# bolek.net
KiCad netlist of a schematic drawn in EAGLE
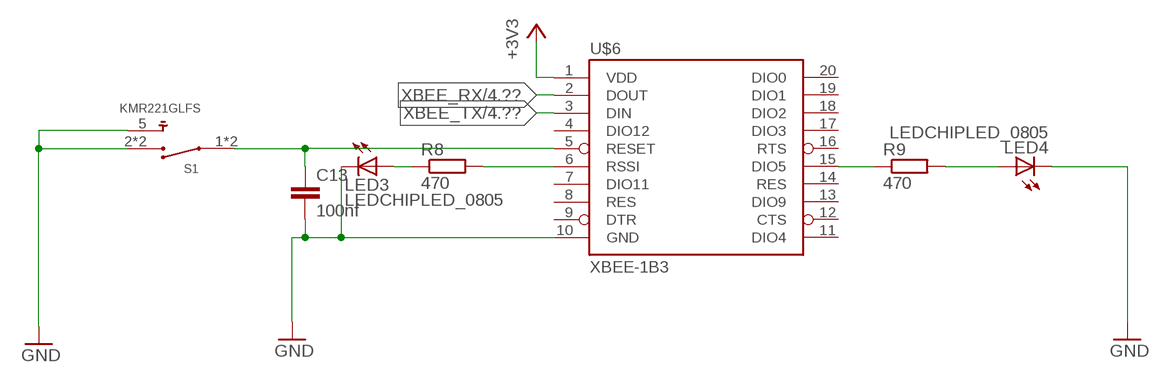
[diagram p0: schematic, sheet 1]
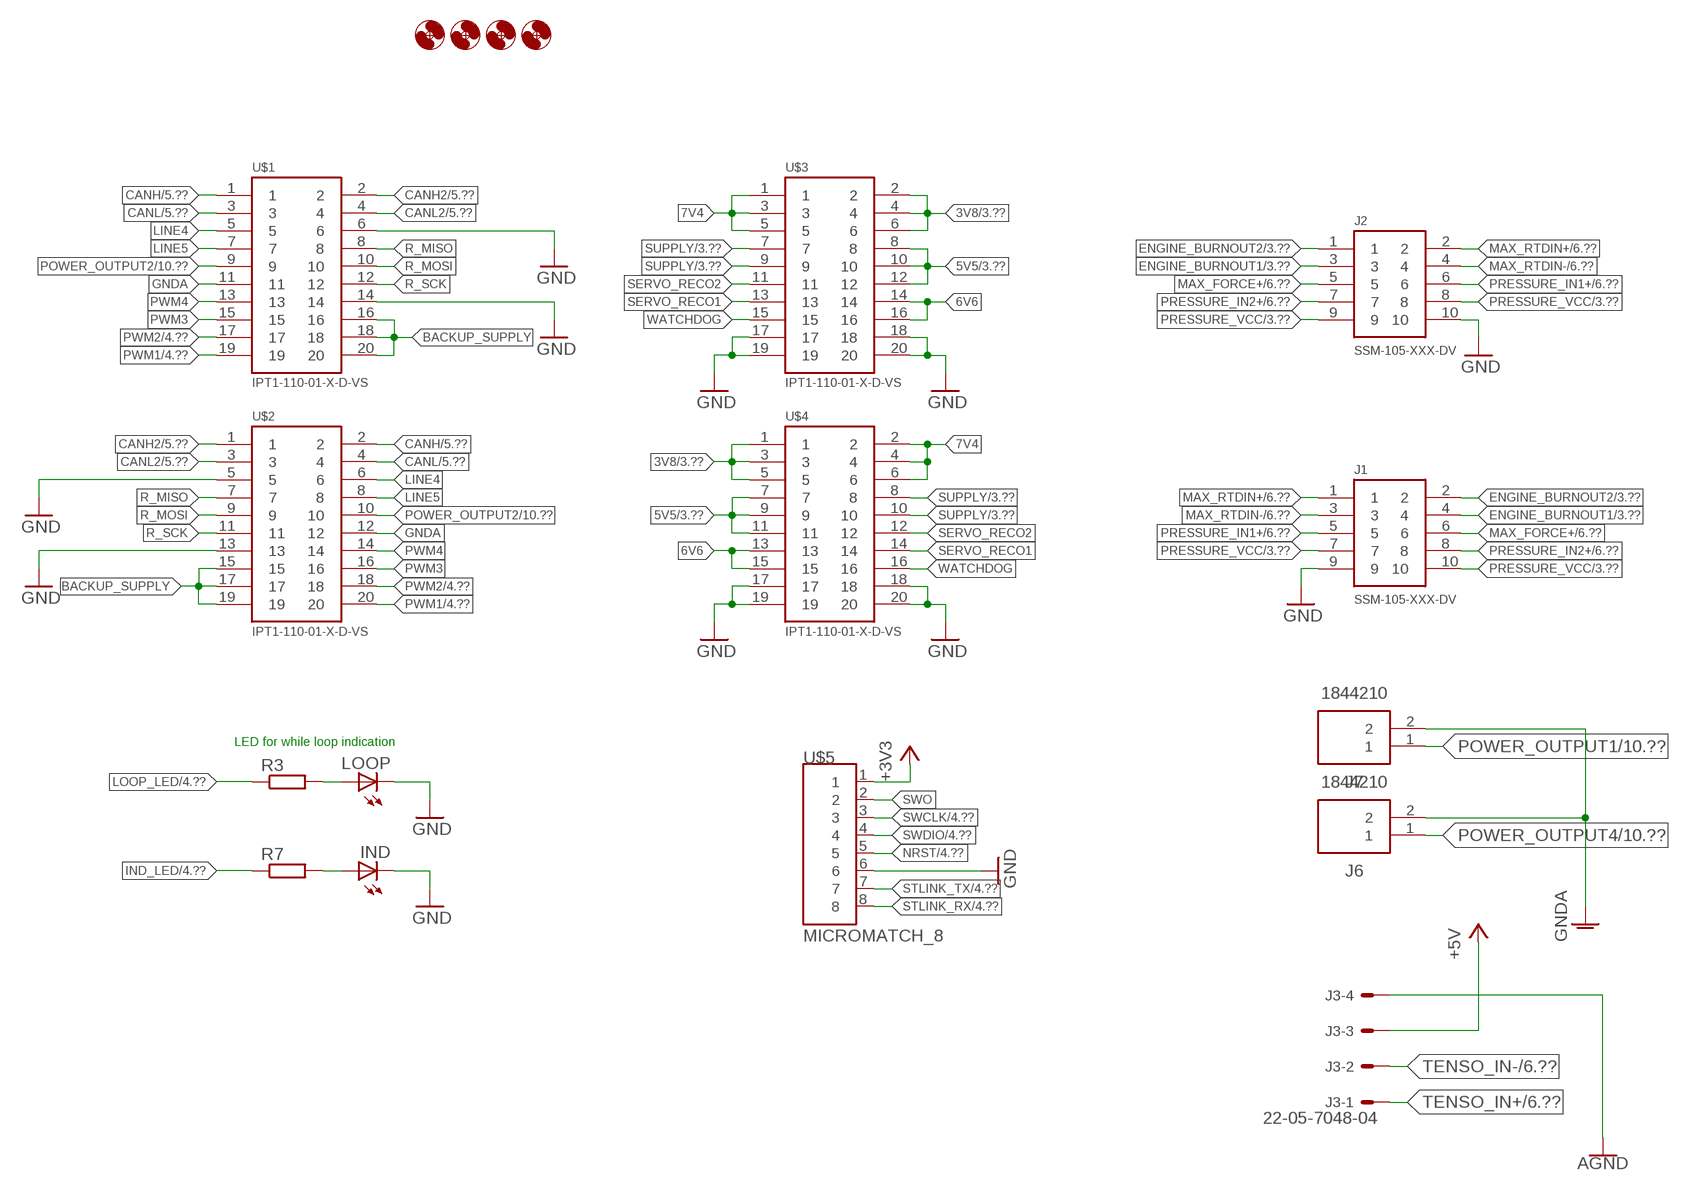
[diagram p1: schematic, sheet 2]
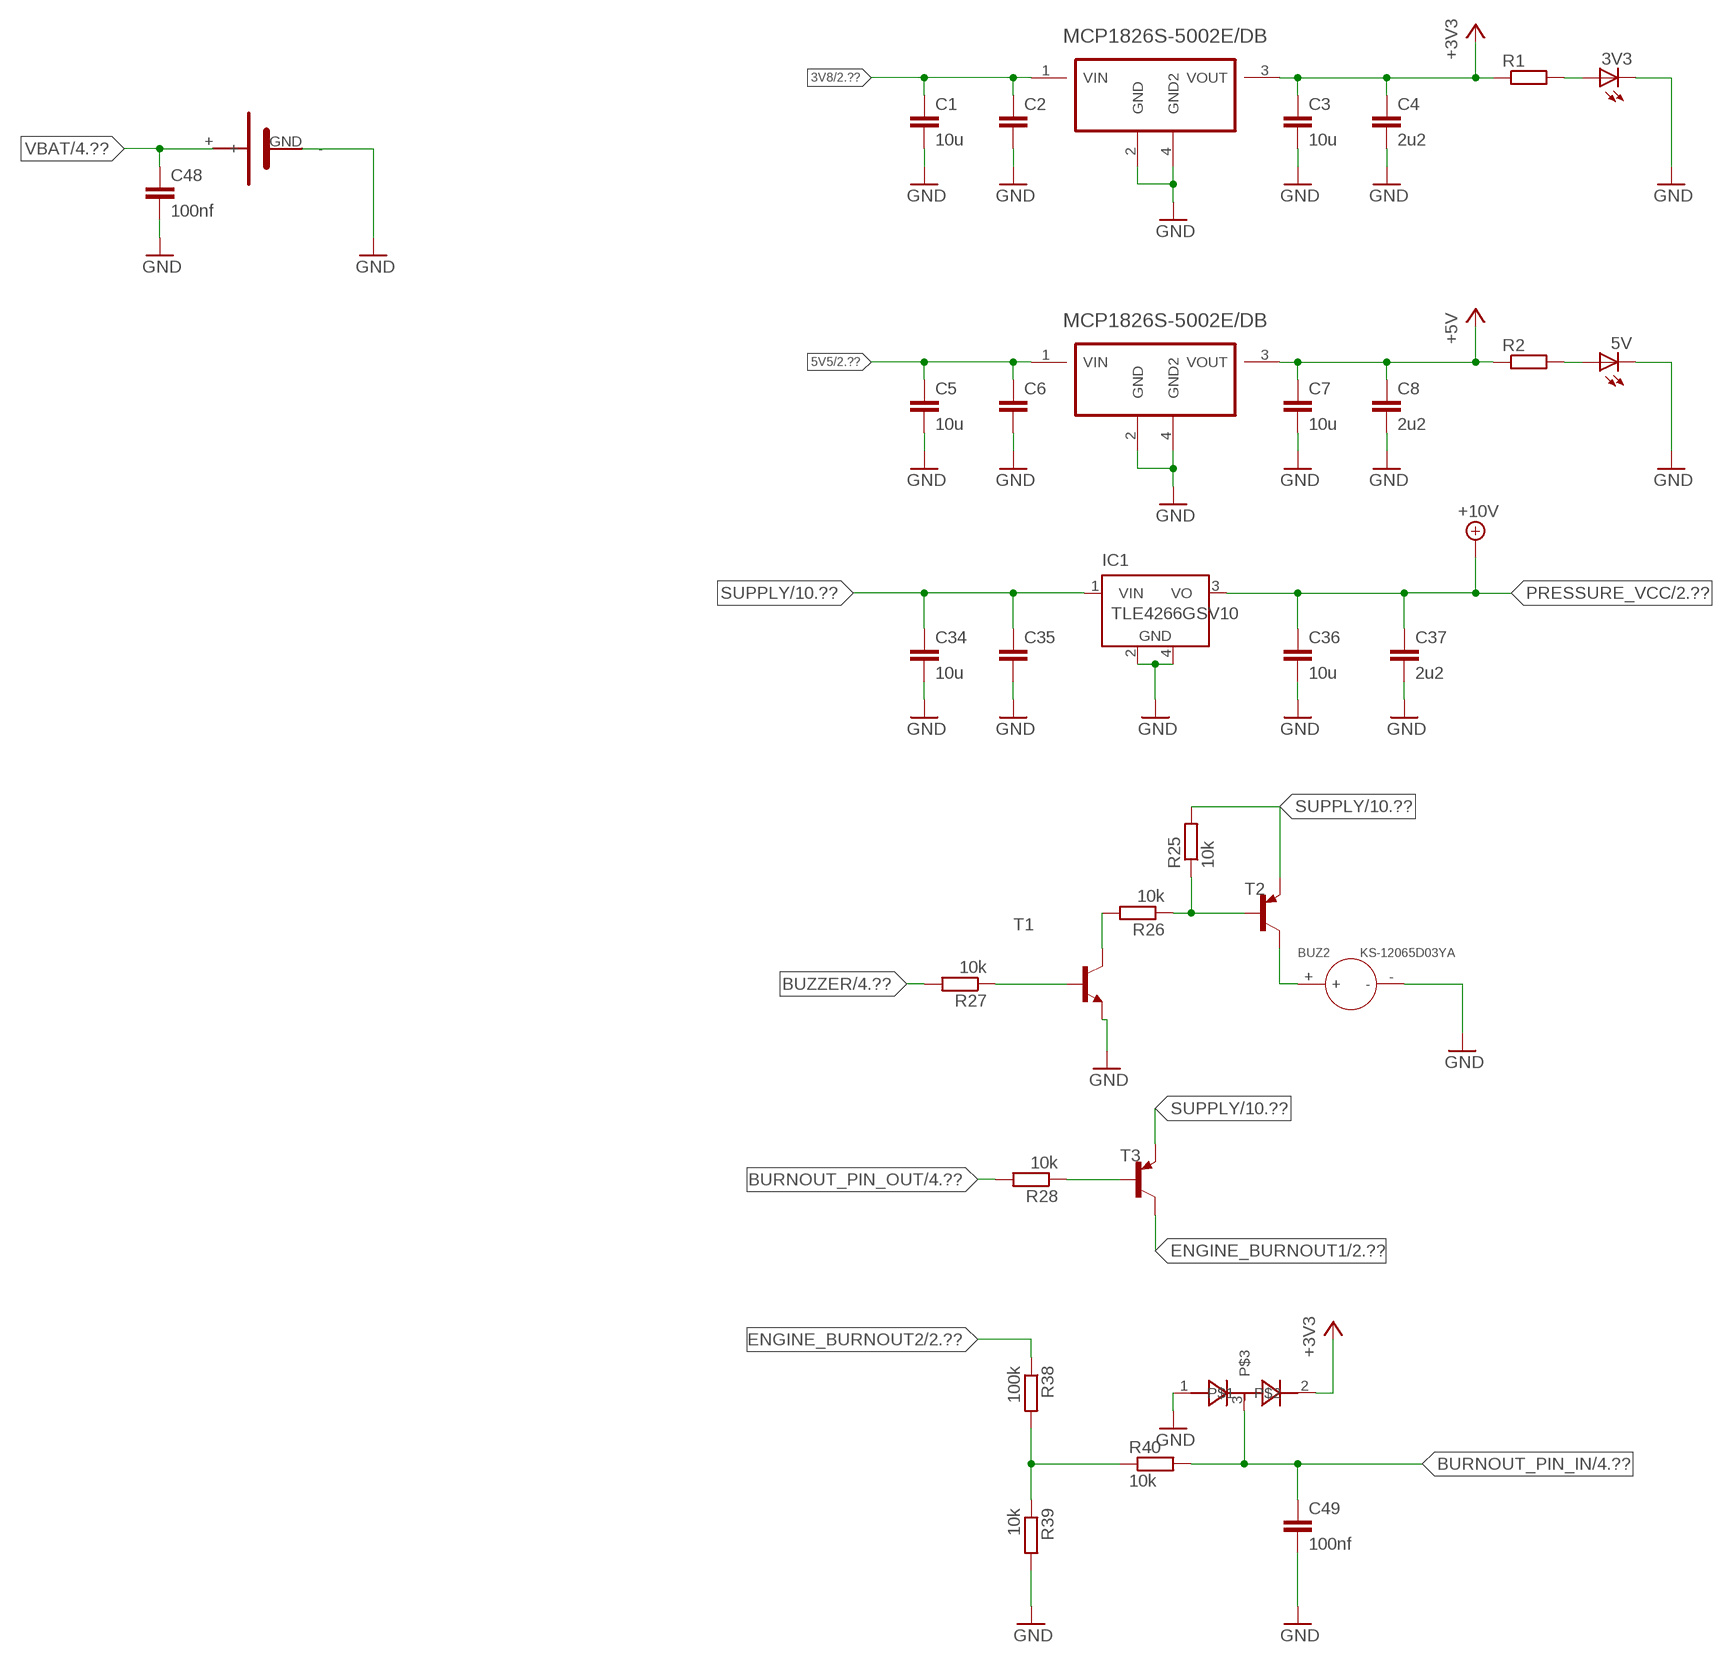
[diagram p2: schematic, sheet 3]
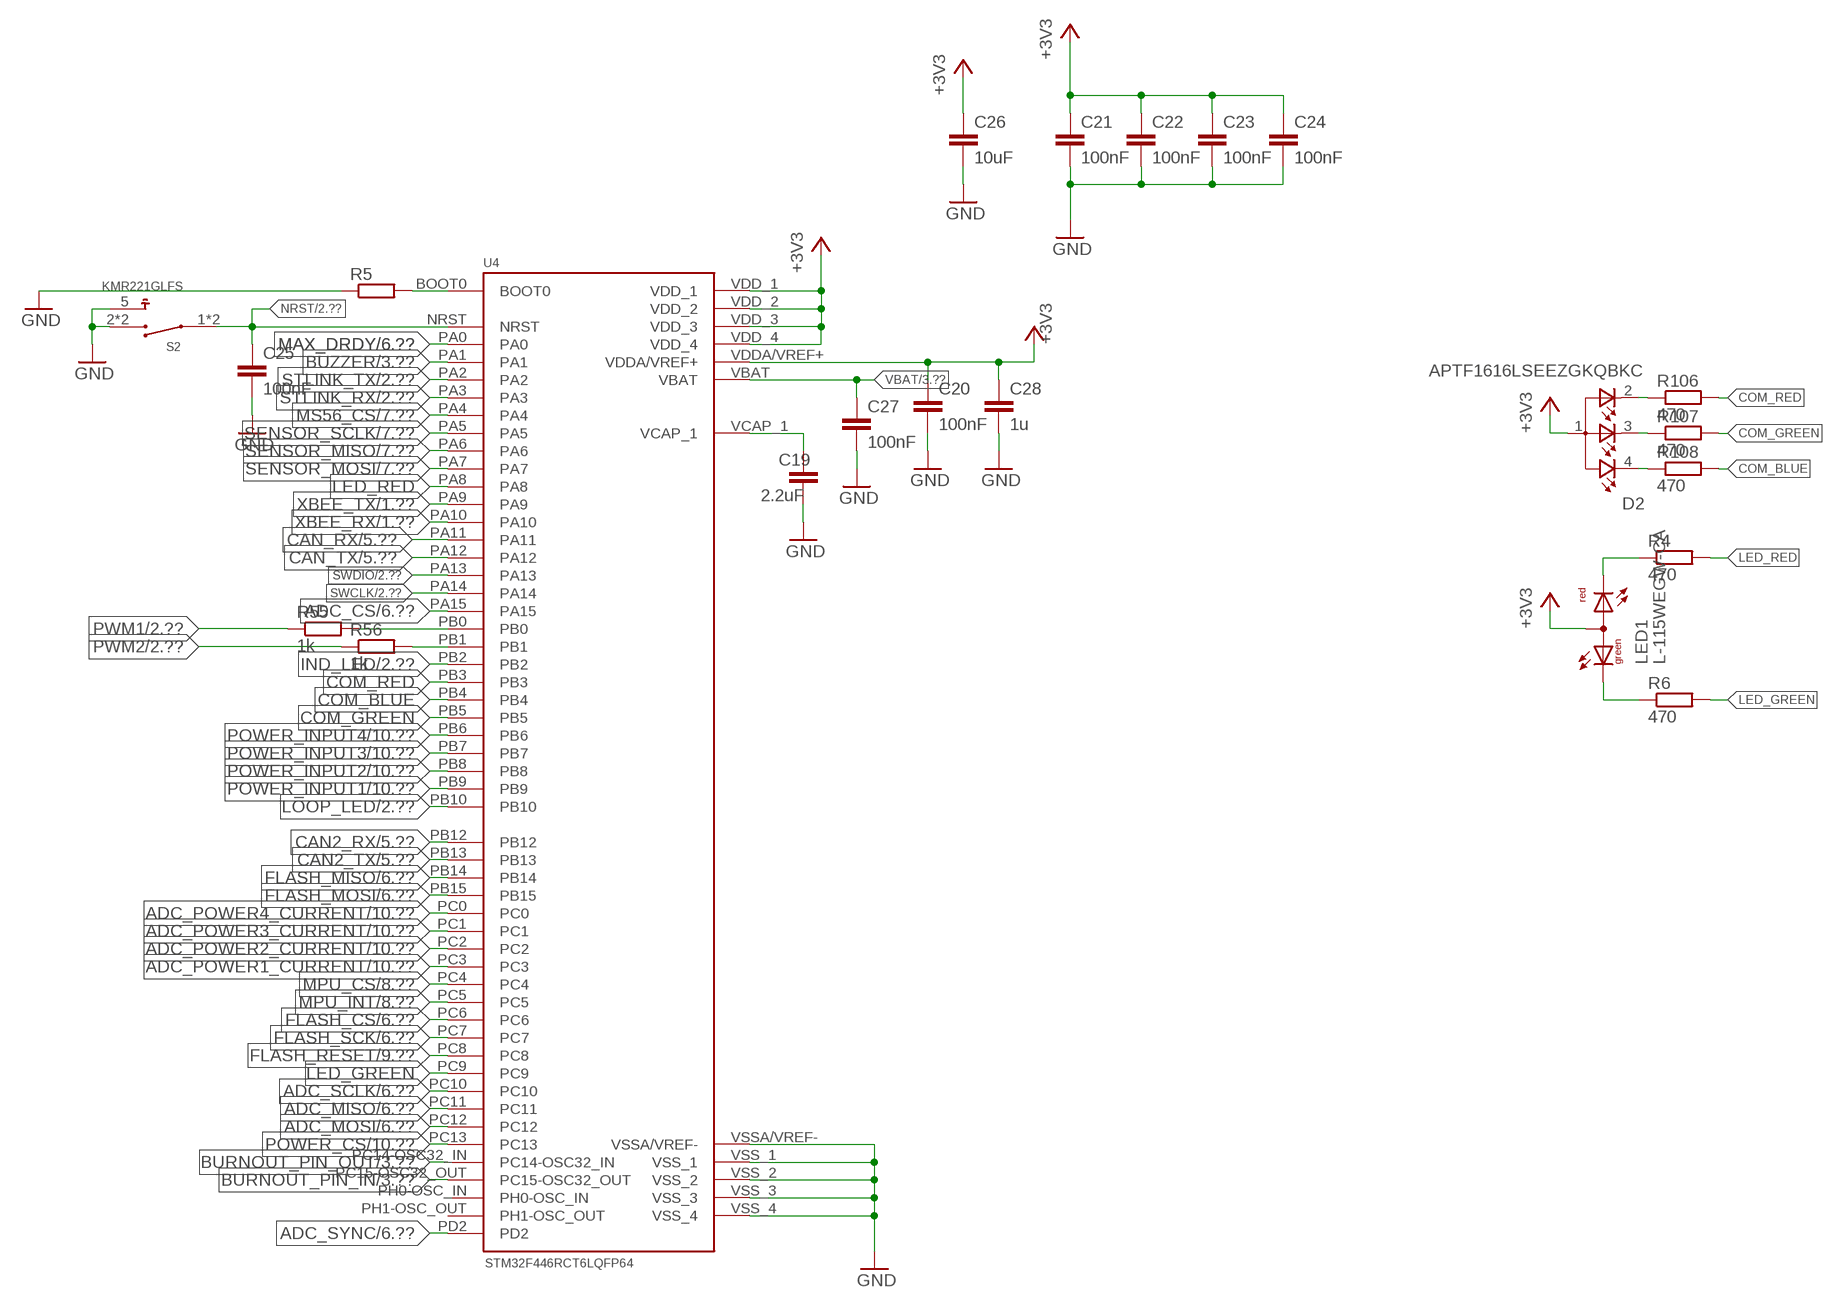
[diagram p3: schematic, sheet 4]
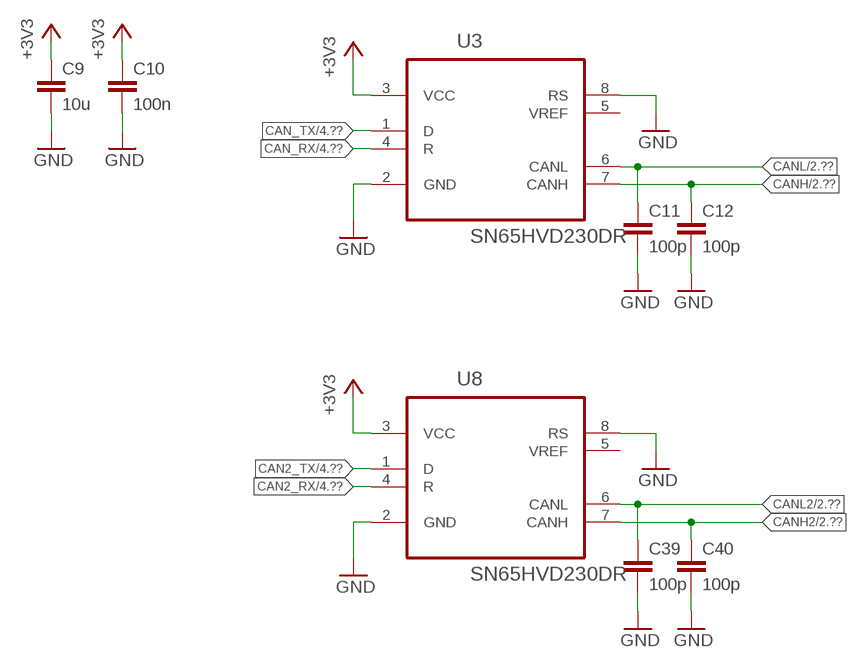
[diagram p4: schematic, sheet 5]
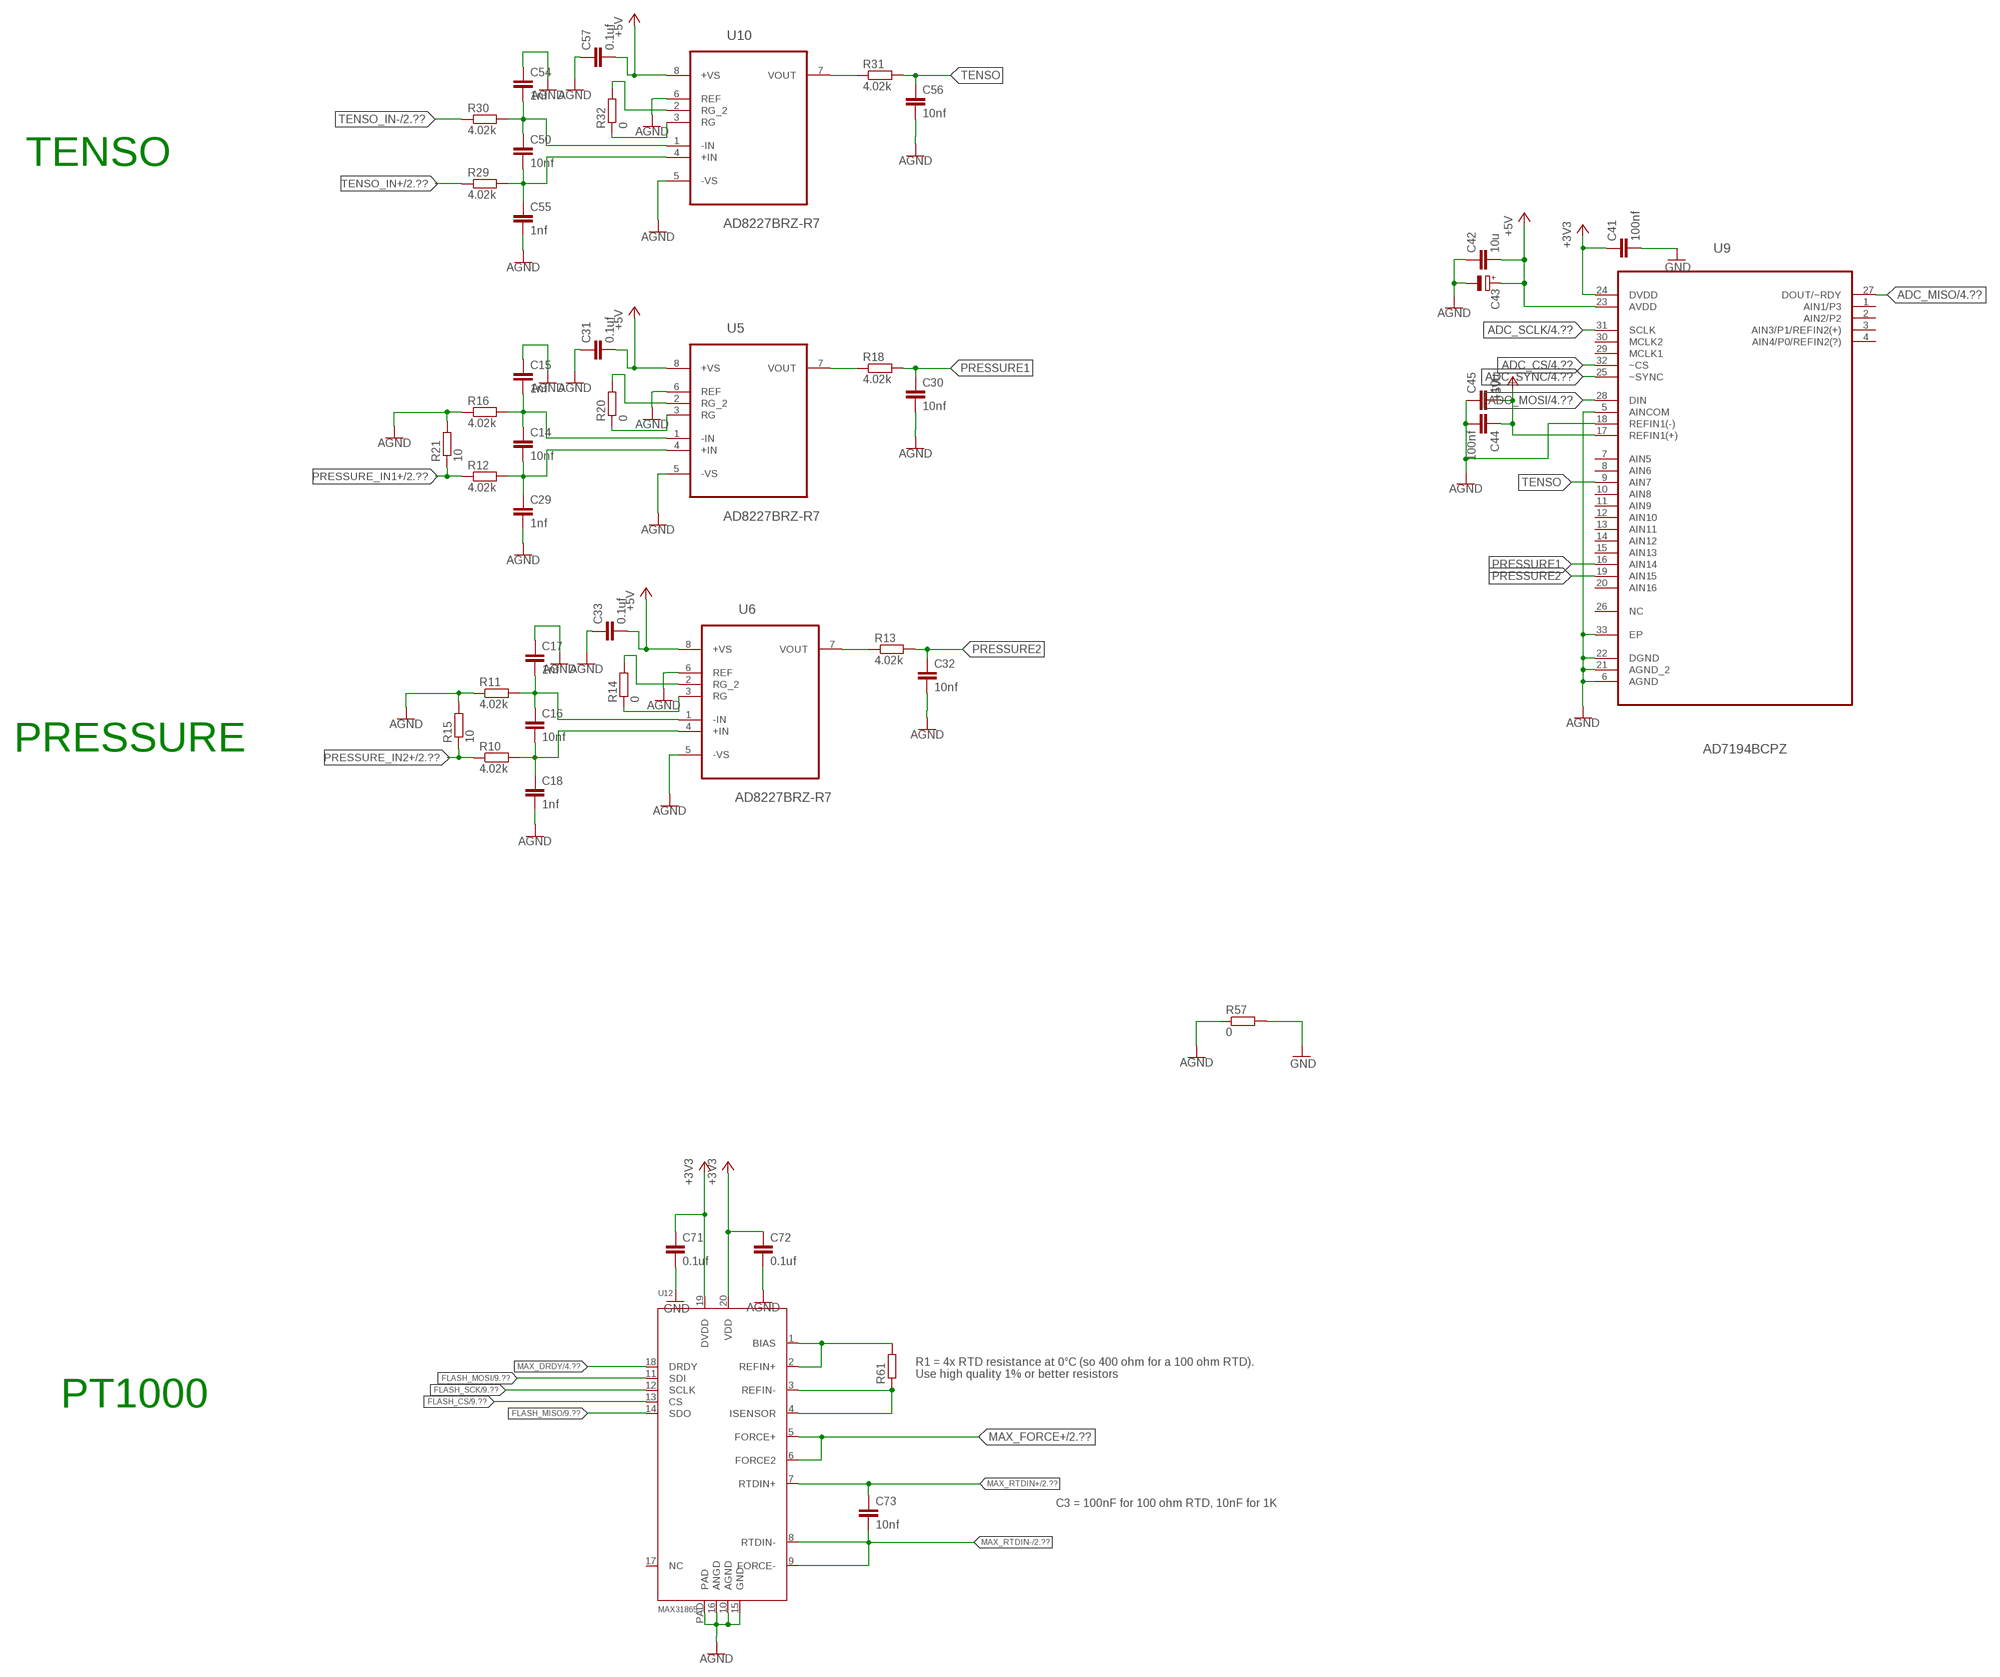
[diagram p5: schematic, sheet 6]
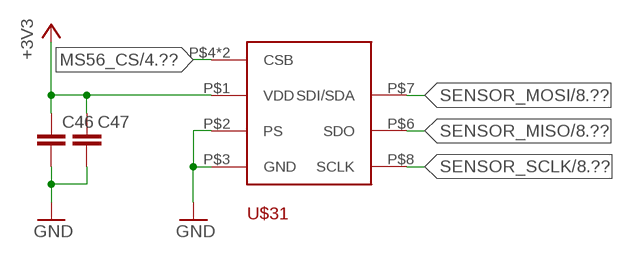
[diagram p6: schematic, sheet 7]
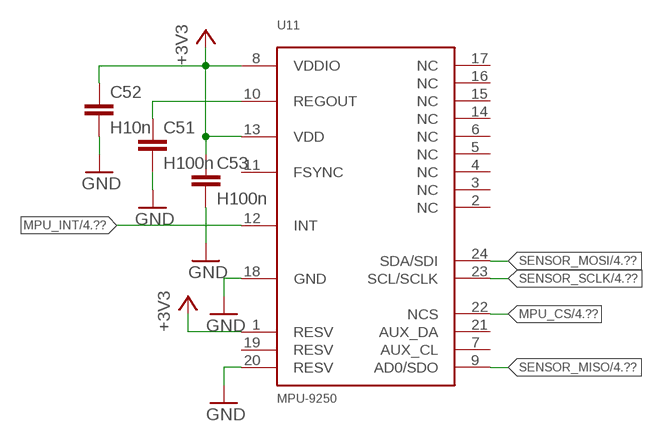
[diagram p7: schematic, sheet 8]
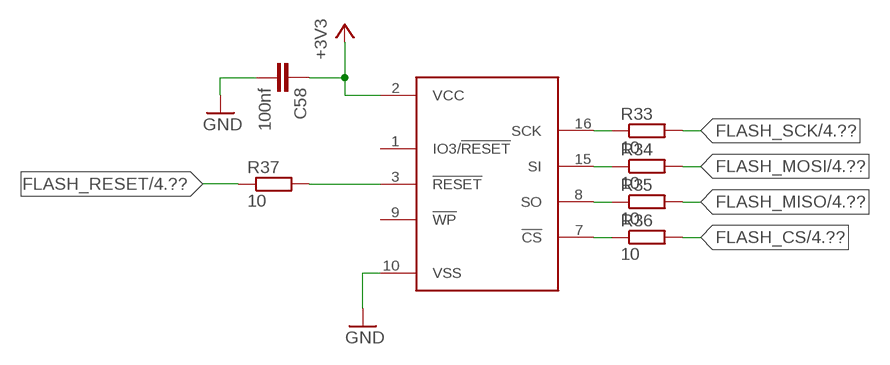
[diagram p8: schematic, sheet 9]
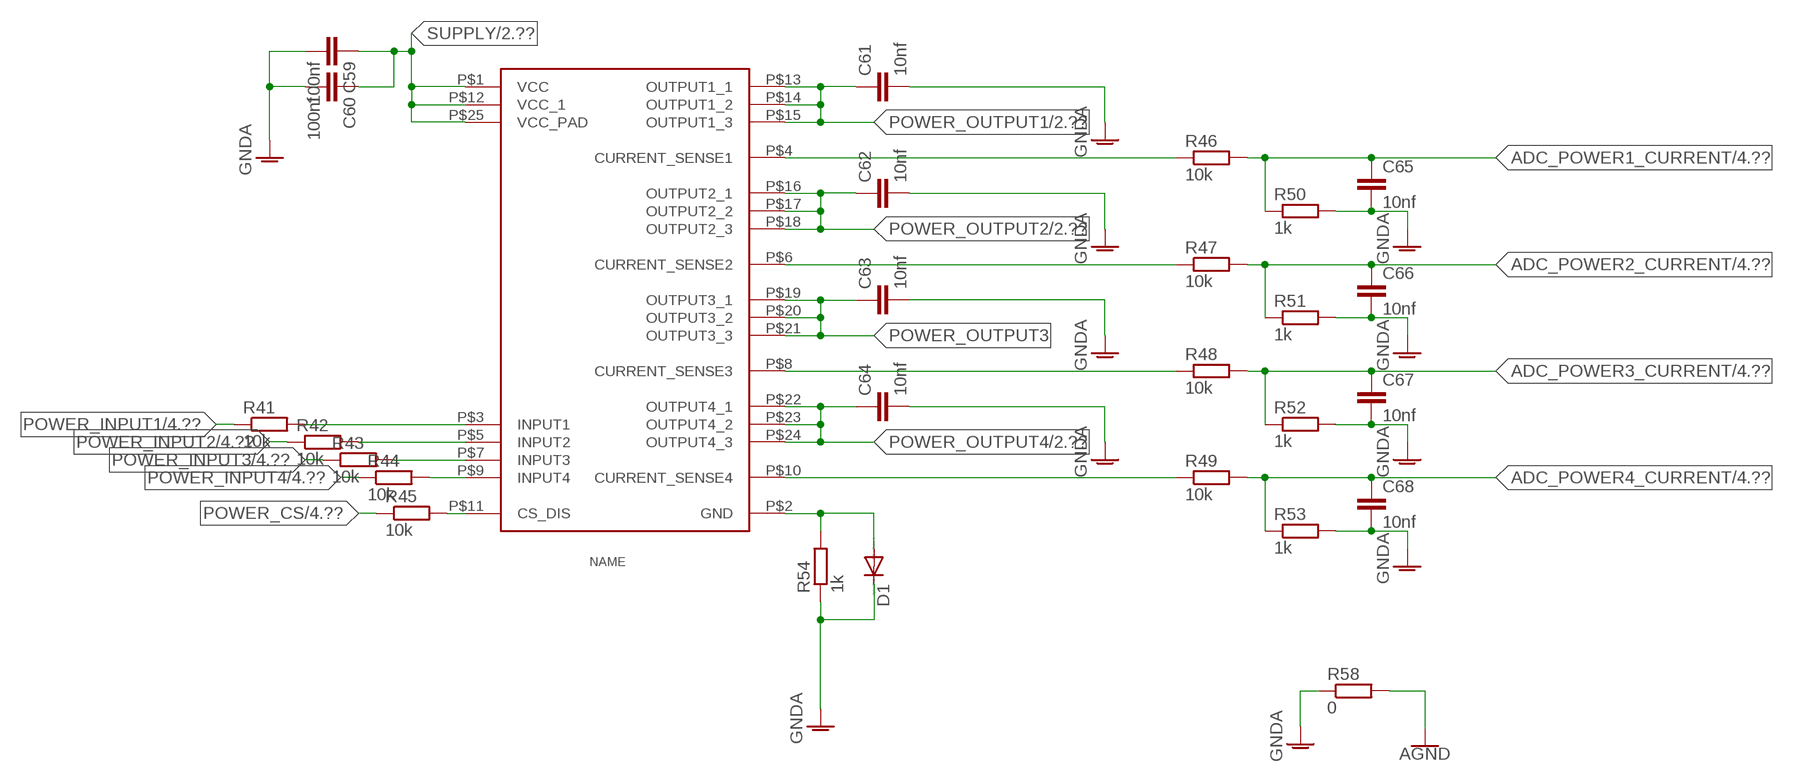
[diagram p9: schematic, sheet 10]

(export (version "E")
  (design (tool "Eeschema 10.0.6"))
  (components
    (comp (ref "C19")
      (value "2.2uF")
      (footprint "eagle-import:C0603K")
      (libsource (lib "eagle-import") (part "rcl_334_C-EUC0603K"))
    )
    (comp (ref "C20")
      (value "100nF")
      (footprint "eagle-import:C0603K")
      (libsource (lib "eagle-import") (part "rcl_334_C-EUC0603K"))
    )
    (comp (ref "C21")
      (value "100nF")
      (footprint "eagle-import:C0603K")
      (libsource (lib "eagle-import") (part "rcl_334_C-EUC0603K"))
    )
    (comp (ref "C22")
      (value "100nF")
      (footprint "eagle-import:C0603K")
      (libsource (lib "eagle-import") (part "rcl_334_C-EUC0603K"))
    )
    (comp (ref "C23")
      (value "100nF")
      (footprint "eagle-import:C0603K")
      (libsource (lib "eagle-import") (part "rcl_334_C-EUC0603K"))
    )
    (comp (ref "C24")
      (value "100nF")
      (footprint "eagle-import:C0603K")
      (libsource (lib "eagle-import") (part "rcl_334_C-EUC0603K"))
    )
    (comp (ref "C25")
      (value "100nF")
      (footprint "eagle-import:C0603K")
      (libsource (lib "eagle-import") (part "rcl_334_C-EUC0603K"))
    )
    (comp (ref "C26")
      (value "10uF")
      (footprint "eagle-import:C0805K")
      (libsource (lib "eagle-import") (part "rcl_334_C-EUC0805K"))
    )
    (comp (ref "C27")
      (value "100nF")
      (footprint "eagle-import:C0603K")
      (libsource (lib "eagle-import") (part "rcl_334_C-EUC0603K"))
    )
    (comp (ref "C28")
      (value "1u")
      (footprint "eagle-import:C0603K")
      (libsource (lib "eagle-import") (part "rcl_334_C-EUC0603K"))
    )
    (comp (ref "D2")
      (value "APTF1616LSEEZGKQBKC")
      (footprint "eagle-import:LEDSC160X160X070-4N")
      (fields (field (name "MF") "Kingbright"))
      (libsource (lib "eagle-import") (part "APTF1616LSEEZGKQBKC"))
    )
    (comp (ref "LED1")
      (value "L-115WEGW-CA")
      (footprint "eagle-import:DUOLED-A-3MM")
      (libsource (lib "eagle-import") (part "L-115WEGW-CA"))
    )
    (comp (ref "R4")
      (value "470")
      (footprint "eagle-import:R0603")
      (libsource (lib "eagle-import") (part "rcl_334_R-EU_R0603"))
    )
    (comp (ref "R5")
      (value "R-EU_R0603")
      (footprint "eagle-import:R0603")
      (libsource (lib "eagle-import") (part "rcl_334_R-EU_R0603"))
    )
    (comp (ref "R6")
      (value "470")
      (footprint "eagle-import:R0603")
      (libsource (lib "eagle-import") (part "rcl_334_R-EU_R0603"))
    )
    (comp (ref "R55")
      (value "1k")
      (footprint "eagle-import:R0603")
      (libsource (lib "eagle-import") (part "rcl_334_R-EU_R0603"))
    )
    (comp (ref "R56")
      (value "1k")
      (footprint "eagle-import:R0603")
      (libsource (lib "eagle-import") (part "rcl_334_R-EU_R0603"))
    )
    (comp (ref "R106")
      (value "470")
      (footprint "eagle-import:R0603")
      (libsource (lib "eagle-import") (part "rcl_334_R-EU_R0603"))
    )
    (comp (ref "R107")
      (value "470")
      (footprint "eagle-import:R0603")
      (libsource (lib "eagle-import") (part "rcl_334_R-EU_R0603"))
    )
    (comp (ref "R108")
      (value "470")
      (footprint "eagle-import:R0603")
      (libsource (lib "eagle-import") (part "rcl_334_R-EU_R0603"))
    )
    (comp (ref "S2")
      (value "KMR221GLFS")
      (footprint "eagle-import:SW_KMR221GLFS")
      (fields (field (name "MF") "C&K Components"))
      (libsource (lib "eagle-import") (part "KMR221GLFS"))
    )
    (comp (ref "U4")
      (value "STM32F446RCT6LQFP64")
      (footprint "eagle-import:QFP50P1290X1290X120-64")
      (libsource (lib "eagle-import") (part "STM32F446RCT6LQFP64"))
    )
    (comp (ref "C51")
      (value "H100n")
      (footprint "eagle-import:C0603K")
      (libsource (lib "eagle-import") (part "rcl_334_C-EUC0603K"))
    )
    (comp (ref "C52")
      (value "H10n")
      (footprint "eagle-import:C0603K")
      (libsource (lib "eagle-import") (part "rcl_334_C-EUC0603K"))
    )
    (comp (ref "C53")
      (value "H100n")
      (footprint "eagle-import:C0603K")
      (libsource (lib "eagle-import") (part "rcl_334_C-EUC0603K"))
    )
    (comp (ref "U11")
      (value "MPU-9250")
      (footprint "eagle-import:MPU-9250")
      (fields (field (name "MF") "InvenSense"))
      (libsource (lib "eagle-import") (part "MPU-9250"))
    )
    (comp (ref "C58")
      (value "100nf")
      (footprint "eagle-import:C0603")
      (libsource (lib "eagle-import") (part "rcl_334_C-EUC0603"))
    )
    (comp (ref "R33")
      (value "10")
      (footprint "eagle-import:R0603")
      (libsource (lib "eagle-import") (part "rcl_334_R-EU_R0603"))
    )
    (comp (ref "R34")
      (value "10")
      (footprint "eagle-import:R0603")
      (libsource (lib "eagle-import") (part "rcl_334_R-EU_R0603"))
    )
    (comp (ref "R35")
      (value "10")
      (footprint "eagle-import:R0603")
      (libsource (lib "eagle-import") (part "rcl_334_R-EU_R0603"))
    )
    (comp (ref "R36")
      (value "10")
      (footprint "eagle-import:R0603")
      (libsource (lib "eagle-import") (part "rcl_334_R-EU_R0603"))
    )
    (comp (ref "R37")
      (value "10")
      (footprint "eagle-import:R0603")
      (libsource (lib "eagle-import") (part "rcl_334_R-EU_R0603"))
    )
    (comp (ref "U$39")
      (value "S25FLX")
      (footprint "eagle-import:SOIC16")
      (libsource (lib "eagle-import") (part "S25FLX"))
    )
    (comp (ref "C14")
      (value "10nf")
      (footprint "eagle-import:C0603")
      (libsource (lib "eagle-import") (part "C-EUC0603"))
    )
    (comp (ref "C15")
      (value "1nf")
      (footprint "eagle-import:C0603")
      (libsource (lib "eagle-import") (part "C-EUC0603"))
    )
    (comp (ref "C16")
      (value "10nf")
      (footprint "eagle-import:C0603")
      (libsource (lib "eagle-import") (part "C-EUC0603"))
    )
    (comp (ref "C17")
      (value "1nf")
      (footprint "eagle-import:C0603")
      (libsource (lib "eagle-import") (part "C-EUC0603"))
    )
    (comp (ref "C18")
      (value "1nf")
      (footprint "eagle-import:C0603")
      (libsource (lib "eagle-import") (part "C-EUC0603"))
    )
    (comp (ref "C29")
      (value "1nf")
      (footprint "eagle-import:C0603")
      (libsource (lib "eagle-import") (part "C-EUC0603"))
    )
    (comp (ref "C30")
      (value "10nf")
      (footprint "eagle-import:C0603")
      (libsource (lib "eagle-import") (part "C-EUC0603"))
    )
    (comp (ref "C31")
      (value "0.1uf")
      (footprint "eagle-import:C0603")
      (libsource (lib "eagle-import") (part "C-EUC0603"))
    )
    (comp (ref "C32")
      (value "10nf")
      (footprint "eagle-import:C0603")
      (libsource (lib "eagle-import") (part "C-EUC0603"))
    )
    (comp (ref "C33")
      (value "0.1uf")
      (footprint "eagle-import:C0603")
      (libsource (lib "eagle-import") (part "C-EUC0603"))
    )
    (comp (ref "C41")
      (value "100nf")
      (footprint "eagle-import:C0603K")
      (libsource (lib "eagle-import") (part "rcl_334_C-EUC0603K"))
    )
    (comp (ref "C42")
      (value "10u")
      (footprint "eagle-import:C0805K")
      (libsource (lib "eagle-import") (part "rcl_334_C-EUC0805K"))
    )
    (comp (ref "C43")
      (value "CPOL-EUSMCA")
      (footprint "eagle-import:SMC_A")
      (libsource (lib "eagle-import") (part "CPOL-EUSMCA"))
    )
    (comp (ref "C44")
      (value "100nf")
      (footprint "eagle-import:C0603K")
      (libsource (lib "eagle-import") (part "rcl_334_C-EUC0603K"))
    )
    (comp (ref "C45")
      (value "10u")
      (footprint "eagle-import:C0805K")
      (libsource (lib "eagle-import") (part "rcl_334_C-EUC0805K"))
    )
    (comp (ref "C50")
      (value "10nf")
      (footprint "eagle-import:C0603")
      (libsource (lib "eagle-import") (part "C-EUC0603"))
    )
    (comp (ref "C54")
      (value "1nf")
      (footprint "eagle-import:C0603")
      (libsource (lib "eagle-import") (part "C-EUC0603"))
    )
    (comp (ref "C55")
      (value "1nf")
      (footprint "eagle-import:C0603")
      (libsource (lib "eagle-import") (part "C-EUC0603"))
    )
    (comp (ref "C56")
      (value "10nf")
      (footprint "eagle-import:C0603")
      (libsource (lib "eagle-import") (part "C-EUC0603"))
    )
    (comp (ref "C57")
      (value "0.1uf")
      (footprint "eagle-import:C0603")
      (libsource (lib "eagle-import") (part "C-EUC0603"))
    )
    (comp (ref "C71")
      (value "0.1uf")
      (footprint "eagle-import:C0603")
      (libsource (lib "eagle-import") (part "rcl_334_C-EUC0603"))
    )
    (comp (ref "C72")
      (value "0.1uf")
      (footprint "eagle-import:C0603")
      (libsource (lib "eagle-import") (part "rcl_334_C-EUC0603"))
    )
    (comp (ref "C73")
      (value "10nf")
      (footprint "eagle-import:C0603")
      (libsource (lib "eagle-import") (part "rcl_334_C-EUC0603"))
    )
    (comp (ref "R10")
      (value "4.02k")
      (footprint "eagle-import:R0603")
      (libsource (lib "eagle-import") (part "R-EU_R0603"))
    )
    (comp (ref "R11")
      (value "4.02k")
      (footprint "eagle-import:R0603")
      (libsource (lib "eagle-import") (part "R-EU_R0603"))
    )
    (comp (ref "R12")
      (value "4.02k")
      (footprint "eagle-import:R0603")
      (libsource (lib "eagle-import") (part "R-EU_R0603"))
    )
    (comp (ref "R13")
      (value "4.02k")
      (footprint "eagle-import:R0603")
      (libsource (lib "eagle-import") (part "R-EU_R0603"))
    )
    (comp (ref "R14")
      (value "0")
      (footprint "eagle-import:R0805")
      (libsource (lib "eagle-import") (part "R-EU_R0805"))
    )
    (comp (ref "R15")
      (value "10")
      (footprint "eagle-import:R0603")
      (libsource (lib "eagle-import") (part "R-EU_R0603"))
    )
    (comp (ref "R16")
      (value "4.02k")
      (footprint "eagle-import:R0603")
      (libsource (lib "eagle-import") (part "R-EU_R0603"))
    )
    (comp (ref "R18")
      (value "4.02k")
      (footprint "eagle-import:R0603")
      (libsource (lib "eagle-import") (part "R-EU_R0603"))
    )
    (comp (ref "R20")
      (value "0")
      (footprint "eagle-import:R0805")
      (libsource (lib "eagle-import") (part "R-EU_R0805"))
    )
    (comp (ref "R21")
      (value "10")
      (footprint "eagle-import:R0603")
      (libsource (lib "eagle-import") (part "R-EU_R0603"))
    )
    (comp (ref "R29")
      (value "4.02k")
      (footprint "eagle-import:R0603")
      (libsource (lib "eagle-import") (part "R-EU_R0603"))
    )
    (comp (ref "R30")
      (value "4.02k")
      (footprint "eagle-import:R0603")
      (libsource (lib "eagle-import") (part "R-EU_R0603"))
    )
    (comp (ref "R31")
      (value "4.02k")
      (footprint "eagle-import:R0603")
      (libsource (lib "eagle-import") (part "R-EU_R0603"))
    )
    (comp (ref "R32")
      (value "0")
      (footprint "eagle-import:R0805")
      (libsource (lib "eagle-import") (part "R-EU_R0805"))
    )
    (comp (ref "R57")
      (value "0")
      (footprint "eagle-import:R0603")
      (libsource (lib "eagle-import") (part "rcl_334_R-EU_R0603"))
    )
    (comp (ref "R61")
      (value "R-EU_R0805")
      (footprint "eagle-import:R0805")
      (libsource (lib "eagle-import") (part "rcl_334_R-EU_R0805"))
    )
    (comp (ref "U5")
      (value "AD8227BRZ-R7")
      (footprint "eagle-import:SOIC127P600X175-8N")
      (libsource (lib "eagle-import") (part "AD8227BRZ-R7"))
    )
    (comp (ref "U6")
      (value "AD8227BRZ-R7")
      (footprint "eagle-import:SOIC127P600X175-8N")
      (libsource (lib "eagle-import") (part "AD8227BRZ-R7"))
    )
    (comp (ref "U9")
      (value "AD7194BCPZ")
      (footprint "eagle-import:QFN50P500X500X80-33N")
      (libsource (lib "eagle-import") (part "AD7194BCPZ"))
    )
    (comp (ref "U10")
      (value "AD8227BRZ-R7")
      (footprint "eagle-import:SOIC127P600X175-8N")
      (libsource (lib "eagle-import") (part "AD8227BRZ-R7"))
    )
    (comp (ref "U12")
      (value "MAX31865")
      (footprint "eagle-import:QFN20_4MM_0.65MM")
      (libsource (lib "eagle-import") (part "TEMP_MAX31865"))
    )
    (comp (ref "H1")
      (value "MOUNT-HOLE3.2")
      (footprint "eagle-import:3,2")
      (libsource (lib "eagle-import") (part "MOUNT-HOLE3.2"))
    )
    (comp (ref "H2")
      (value "MOUNT-HOLE3.2")
      (footprint "eagle-import:3,2")
      (libsource (lib "eagle-import") (part "MOUNT-HOLE3.2"))
    )
    (comp (ref "H3")
      (value "MOUNT-HOLE3.2")
      (footprint "eagle-import:3,2")
      (libsource (lib "eagle-import") (part "MOUNT-HOLE3.2"))
    )
    (comp (ref "H4")
      (value "MOUNT-HOLE3.2")
      (footprint "eagle-import:3,2")
      (libsource (lib "eagle-import") (part "MOUNT-HOLE3.2"))
    )
    (comp (ref "IND")
      (value "LEDCHIPLED_0603")
      (footprint "eagle-import:CHIPLED_0603")
      (libsource (lib "eagle-import") (part "LEDCHIPLED_0603"))
    )
    (comp (ref "J1")
      (value "SSM-105-XXX-DV")
      (footprint "eagle-import:SSM-105-XXX-DV")
      (fields (field (name "MF") "Samtec"))
      (libsource (lib "eagle-import") (part "SSM-105-XXX-DV"))
    )
    (comp (ref "J2")
      (value "SSM-105-XXX-DV")
      (footprint "eagle-import:SSM-105-XXX-DV")
      (fields (field (name "MF") "Samtec"))
      (libsource (lib "eagle-import") (part "SSM-105-XXX-DV"))
    )
    (comp (ref "J3")
      (value "22-05-7048-04")
      (footprint "eagle-import:7395-04")
      (fields (field (name "MF") "MOLEX"))
      (libsource (lib "eagle-import") (part "22-?-0405-7048"))
    )
    (comp (ref "J6")
      (value "1844210")
      (footprint "eagle-import:SHDR2W100P0X350_1X2_840X920X72")
      (fields (field (name "RS_PART_NUMBER") "8042248"))
      (libsource (lib "eagle-import") (part "1844210"))
    )
    (comp (ref "J7")
      (value "1844210")
      (footprint "eagle-import:SHDR2W100P0X350_1X2_840X920X72")
      (fields (field (name "RS_PART_NUMBER") "8042248"))
      (libsource (lib "eagle-import") (part "1844210"))
    )
    (comp (ref "LOOP")
      (value "LEDCHIPLED_0603")
      (footprint "eagle-import:CHIPLED_0603")
      (libsource (lib "eagle-import") (part "LEDCHIPLED_0603"))
    )
    (comp (ref "R3")
      (value "R-EU_R0603")
      (footprint "eagle-import:R0603")
      (libsource (lib "eagle-import") (part "rcl_334_R-EU_R0603"))
    )
    (comp (ref "R7")
      (value "R-EU_R0603")
      (footprint "eagle-import:R0603")
      (libsource (lib "eagle-import") (part "rcl_334_R-EU_R0603"))
    )
    (comp (ref "U$1")
      (value "IPT1-110-01-X-D-VS")
      (footprint "eagle-import:IPT1-110-01-X-D-VS")
      (fields (field (name "MF") "Samtec") (field (name "MP") "IPT1-110--01-S-D-VS-"))
      (libsource (lib "eagle-import") (part "IPT1-110-01-X-D-VS"))
    )
    (comp (ref "U$2")
      (value "IPT1-110-01-X-D-VS")
      (footprint "eagle-import:IPT1-110-01-X-D-VS")
      (fields (field (name "MF") "Samtec") (field (name "MP") "IPT1-110--01-S-D-VS-"))
      (libsource (lib "eagle-import") (part "IPT1-110-01-X-D-VS"))
    )
    (comp (ref "U$3")
      (value "IPT1-110-01-X-D-VS")
      (footprint "eagle-import:IPT1-110-01-X-D-VS")
      (fields (field (name "MF") "Samtec") (field (name "MP") "IPT1-110--01-S-D-VS-"))
      (libsource (lib "eagle-import") (part "IPT1-110-01-X-D-VS"))
    )
    (comp (ref "U$4")
      (value "IPT1-110-01-X-D-VS")
      (footprint "eagle-import:IPT1-110-01-X-D-VS")
      (fields (field (name "MF") "Samtec") (field (name "MP") "IPT1-110--01-S-D-VS-"))
      (libsource (lib "eagle-import") (part "IPT1-110-01-X-D-VS"))
    )
    (comp (ref "U$5")
      (value "MICROMATCH_8")
      (footprint "eagle-import:MICROMATCH_8")
      (libsource (lib "eagle-import") (part "MICROMATCH_8"))
    )
    (comp (ref "C59")
      (value "100nf")
      (footprint "eagle-import:C0603")
      (libsource (lib "eagle-import") (part "rcl_334_C-EUC0603"))
    )
    (comp (ref "C60")
      (value "100nf")
      (footprint "eagle-import:C0603")
      (libsource (lib "eagle-import") (part "rcl_334_C-EUC0603"))
    )
    (comp (ref "C61")
      (value "10nf")
      (footprint "eagle-import:C0603")
      (libsource (lib "eagle-import") (part "rcl_334_C-EUC0603"))
    )
    (comp (ref "C62")
      (value "10nf")
      (footprint "eagle-import:C0603")
      (libsource (lib "eagle-import") (part "rcl_334_C-EUC0603"))
    )
    (comp (ref "C63")
      (value "10nf")
      (footprint "eagle-import:C0603")
      (libsource (lib "eagle-import") (part "rcl_334_C-EUC0603"))
    )
    (comp (ref "C64")
      (value "10nf")
      (footprint "eagle-import:C0603")
      (libsource (lib "eagle-import") (part "rcl_334_C-EUC0603"))
    )
    (comp (ref "C65")
      (value "10nf")
      (footprint "eagle-import:C0603")
      (libsource (lib "eagle-import") (part "rcl_334_C-EUC0603"))
    )
    (comp (ref "C66")
      (value "10nf")
      (footprint "eagle-import:C0603")
      (libsource (lib "eagle-import") (part "rcl_334_C-EUC0603"))
    )
    (comp (ref "C67")
      (value "10nf")
      (footprint "eagle-import:C0603")
      (libsource (lib "eagle-import") (part "rcl_334_C-EUC0603"))
    )
    (comp (ref "C68")
      (value "10nf")
      (footprint "eagle-import:C0603")
      (libsource (lib "eagle-import") (part "rcl_334_C-EUC0603"))
    )
    (comp (ref "D1")
      (value "DIODE-SOD123")
      (footprint "eagle-import:SOD123")
      (libsource (lib "eagle-import") (part "DIODE-SOD123"))
    )
    (comp (ref "R41")
      (value "10k")
      (footprint "eagle-import:R0603")
      (libsource (lib "eagle-import") (part "rcl_334_R-EU_R0603"))
    )
    (comp (ref "R42")
      (value "10k")
      (footprint "eagle-import:R0603")
      (libsource (lib "eagle-import") (part "rcl_334_R-EU_R0603"))
    )
    (comp (ref "R43")
      (value "10k")
      (footprint "eagle-import:R0603")
      (libsource (lib "eagle-import") (part "rcl_334_R-EU_R0603"))
    )
    (comp (ref "R44")
      (value "10k")
      (footprint "eagle-import:R0603")
      (libsource (lib "eagle-import") (part "rcl_334_R-EU_R0603"))
    )
    (comp (ref "R45")
      (value "10k")
      (footprint "eagle-import:R0603")
      (libsource (lib "eagle-import") (part "rcl_334_R-EU_R0603"))
    )
    (comp (ref "R46")
      (value "10k")
      (footprint "eagle-import:R0603")
      (libsource (lib "eagle-import") (part "rcl_334_R-EU_R0603"))
    )
    (comp (ref "R47")
      (value "10k")
      (footprint "eagle-import:R0603")
      (libsource (lib "eagle-import") (part "rcl_334_R-EU_R0603"))
    )
    (comp (ref "R48")
      (value "10k")
      (footprint "eagle-import:R0603")
      (libsource (lib "eagle-import") (part "rcl_334_R-EU_R0603"))
    )
    (comp (ref "R49")
      (value "10k")
      (footprint "eagle-import:R0603")
      (libsource (lib "eagle-import") (part "rcl_334_R-EU_R0603"))
    )
    (comp (ref "R50")
      (value "1k")
      (footprint "eagle-import:R0603")
      (libsource (lib "eagle-import") (part "rcl_334_R-EU_R0603"))
    )
    (comp (ref "R51")
      (value "1k")
      (footprint "eagle-import:R0603")
      (libsource (lib "eagle-import") (part "rcl_334_R-EU_R0603"))
    )
    (comp (ref "R52")
      (value "1k")
      (footprint "eagle-import:R0603")
      (libsource (lib "eagle-import") (part "rcl_334_R-EU_R0603"))
    )
    (comp (ref "R53")
      (value "1k")
      (footprint "eagle-import:R0603")
      (libsource (lib "eagle-import") (part "rcl_334_R-EU_R0603"))
    )
    (comp (ref "R54")
      (value "1k")
      (footprint "eagle-import:R0603")
      (libsource (lib "eagle-import") (part "rcl_334_R-EU_R0603"))
    )
    (comp (ref "R58")
      (value "0")
      (footprint "eagle-import:R0603")
      (libsource (lib "eagle-import") (part "rcl_334_R-EU_R0603"))
    )
    (comp (ref "VNQ5027AK-E1")
      (value "VNQ5027AK-E")
      (footprint "eagle-import:POWERSSO-24")
      (libsource (lib "eagle-import") (part "VNQ5027AK-E"))
    )
    (comp (ref "C46")
      (value "C-EUC0603")
      (footprint "eagle-import:C0603")
      (libsource (lib "eagle-import") (part "rcl_334_C-EUC0603"))
    )
    (comp (ref "C47")
      (value "C-EUC0603")
      (footprint "eagle-import:C0603")
      (libsource (lib "eagle-import") (part "rcl_334_C-EUC0603"))
    )
    (comp (ref "U$31")
      (value "MS56XX")
      (footprint "eagle-import:MS56XX")
      (libsource (lib "eagle-import") (part "MS56XX"))
    )
    (comp (ref "C9")
      (value "10u")
      (footprint "eagle-import:C0805K")
      (libsource (lib "eagle-import") (part "rcl_334_C-EUC0805K"))
    )
    (comp (ref "C10")
      (value "100n")
      (footprint "eagle-import:C0603K")
      (libsource (lib "eagle-import") (part "rcl_334_C-EUC0603K"))
    )
    (comp (ref "C11")
      (value "100p")
      (footprint "eagle-import:C0603K")
      (libsource (lib "eagle-import") (part "rcl_334_C-EUC0603K"))
    )
    (comp (ref "C12")
      (value "100p")
      (footprint "eagle-import:C0603K")
      (libsource (lib "eagle-import") (part "rcl_334_C-EUC0603K"))
    )
    (comp (ref "C39")
      (value "100p")
      (footprint "eagle-import:C0603K")
      (libsource (lib "eagle-import") (part "rcl_334_C-EUC0603K"))
    )
    (comp (ref "C40")
      (value "100p")
      (footprint "eagle-import:C0603K")
      (libsource (lib "eagle-import") (part "rcl_334_C-EUC0603K"))
    )
    (comp (ref "U3")
      (value "SN65HVD230DR")
      (footprint "eagle-import:SOIC127P600X175-8N")
      (fields (field (name "MF") "Texas Instruments"))
      (libsource (lib "eagle-import") (part "SN65HVD230DR"))
    )
    (comp (ref "U8")
      (value "SN65HVD230DR")
      (footprint "eagle-import:SOIC127P600X175-8N")
      (fields (field (name "MF") "Texas Instruments"))
      (libsource (lib "eagle-import") (part "SN65HVD230DR"))
    )
    (comp (ref "C13")
      (value "100nf")
      (footprint "eagle-import:C0603")
      (libsource (lib "eagle-import") (part "rcl_334_C-EUC0603"))
    )
    (comp (ref "LED3")
      (value "LEDCHIPLED_0805")
      (footprint "eagle-import:CHIPLED_0805")
      (libsource (lib "eagle-import") (part "audio amplifier example_970892_LEDCHIPLED_0805"))
    )
    (comp (ref "LED4")
      (value "LEDCHIPLED_0805")
      (footprint "eagle-import:CHIPLED_0805")
      (libsource (lib "eagle-import") (part "audio amplifier example_970892_LEDCHIPLED_0805"))
    )
    (comp (ref "R8")
      (value "470")
      (footprint "eagle-import:R0603")
      (libsource (lib "eagle-import") (part "resistor_348_R-EU_R0603"))
    )
    (comp (ref "R9")
      (value "470")
      (footprint "eagle-import:R0603")
      (libsource (lib "eagle-import") (part "resistor_348_R-EU_R0603"))
    )
    (comp (ref "S1")
      (value "KMR221GLFS")
      (footprint "eagle-import:SW_KMR221GLFS")
      (fields (field (name "MF") "C&K Components"))
      (libsource (lib "eagle-import") (part "KMR221GLFS"))
    )
    (comp (ref "U$6")
      (value "XBEE-1B3")
      (footprint "eagle-import:XBEE-SMD")
      (libsource (lib "eagle-import") (part "XBEE-1B3"))
    )
    (comp (ref "3V3")
      (value "LEDCHIPLED_0603")
      (footprint "eagle-import:CHIPLED_0603")
      (libsource (lib "eagle-import") (part "LEDCHIPLED_0603"))
    )
    (comp (ref "5V")
      (value "LEDCHIPLED_0603")
      (footprint "eagle-import:CHIPLED_0603")
      (libsource (lib "eagle-import") (part "LEDCHIPLED_0603"))
    )
    (comp (ref "BUZ2")
      (value "KS-12065D03YA")
      (footprint "eagle-import:BZ2-7.6-D12.0XH6.5MM")
      (libsource (lib "eagle-import") (part "DIP-BUZZER-3V(KS-12065D03YA)"))
    )
    (comp (ref "C1")
      (value "10u")
      (footprint "eagle-import:C0805K")
      (libsource (lib "eagle-import") (part "rcl_334_C-EUC0805K"))
    )
    (comp (ref "C2")
      (value "C-EUC0805K")
      (footprint "eagle-import:C0805K")
      (libsource (lib "eagle-import") (part "rcl_334_C-EUC0805K"))
    )
    (comp (ref "C3")
      (value "10u")
      (footprint "eagle-import:C0805K")
      (libsource (lib "eagle-import") (part "rcl_334_C-EUC0805K"))
    )
    (comp (ref "C4")
      (value "2u2")
      (footprint "eagle-import:C0805K")
      (libsource (lib "eagle-import") (part "rcl_334_C-EUC0805K"))
    )
    (comp (ref "C5")
      (value "10u")
      (footprint "eagle-import:C0805K")
      (libsource (lib "eagle-import") (part "rcl_334_C-EUC0805K"))
    )
    (comp (ref "C6")
      (value "C-EUC0805K")
      (footprint "eagle-import:C0805K")
      (libsource (lib "eagle-import") (part "rcl_334_C-EUC0805K"))
    )
    (comp (ref "C7")
      (value "10u")
      (footprint "eagle-import:C0805K")
      (libsource (lib "eagle-import") (part "rcl_334_C-EUC0805K"))
    )
    (comp (ref "C8")
      (value "2u2")
      (footprint "eagle-import:C0805K")
      (libsource (lib "eagle-import") (part "rcl_334_C-EUC0805K"))
    )
    (comp (ref "C34")
      (value "10u")
      (footprint "eagle-import:C0805K")
      (libsource (lib "eagle-import") (part "rcl_334_C-EUC0805K"))
    )
    (comp (ref "C35")
      (value "C-EUC0805K")
      (footprint "eagle-import:C0805K")
      (libsource (lib "eagle-import") (part "rcl_334_C-EUC0805K"))
    )
    (comp (ref "C36")
      (value "10u")
      (footprint "eagle-import:C0805K")
      (libsource (lib "eagle-import") (part "rcl_334_C-EUC0805K"))
    )
    (comp (ref "C37")
      (value "2u2")
      (footprint "eagle-import:C0805K")
      (libsource (lib "eagle-import") (part "rcl_334_C-EUC0805K"))
    )
    (comp (ref "C48")
      (value "100nf")
      (footprint "eagle-import:C0805K")
      (libsource (lib "eagle-import") (part "rcl_334_C-EUC0805K"))
    )
    (comp (ref "C49")
      (value "100nf")
      (footprint "eagle-import:C0603")
      (libsource (lib "eagle-import") (part "rcl_334_C-EUC0603"))
    )
    (comp (ref "IC1")
      (value "TLE4266GSV10")
      (footprint "eagle-import:SOT223")
      (fields (field (name "MF") "NATIONAL SEMICONDUCTOR") (field (name "MPN") "LM2936MP-5.0/NOPB"))
      (libsource (lib "eagle-import") (part "LM2936MP?-5.0"))
    )
    (comp (ref "R1")
      (value "R-EU_R0603")
      (footprint "eagle-import:R0603")
      (libsource (lib "eagle-import") (part "rcl_334_R-EU_R0603"))
    )
    (comp (ref "R2")
      (value "R-EU_R0603")
      (footprint "eagle-import:R0603")
      (libsource (lib "eagle-import") (part "rcl_334_R-EU_R0603"))
    )
    (comp (ref "R25")
      (value "10k")
      (footprint "eagle-import:R0603")
      (libsource (lib "eagle-import") (part "rcl_334_R-EU_R0603"))
    )
    (comp (ref "R26")
      (value "10k")
      (footprint "eagle-import:R0603")
      (libsource (lib "eagle-import") (part "rcl_334_R-EU_R0603"))
    )
    (comp (ref "R27")
      (value "10k")
      (footprint "eagle-import:R0603")
      (libsource (lib "eagle-import") (part "rcl_334_R-EU_R0603"))
    )
    (comp (ref "R28")
      (value "10k")
      (footprint "eagle-import:R0603")
      (libsource (lib "eagle-import") (part "rcl_334_R-EU_R0603"))
    )
    (comp (ref "R38")
      (value "100k")
      (footprint "eagle-import:R0603")
      (libsource (lib "eagle-import") (part "rcl_334_R-EU_R0603"))
    )
    (comp (ref "R39")
      (value "10k")
      (footprint "eagle-import:R0603")
      (libsource (lib "eagle-import") (part "rcl_334_R-EU_R0603"))
    )
    (comp (ref "R40")
      (value "10k")
      (footprint "eagle-import:R0603")
      (libsource (lib "eagle-import") (part "rcl_334_R-EU_R0603"))
    )
    (comp (ref "T1")
      (value "BCW81-NPN-SOT23-BEC")
      (footprint "eagle-import:SOT23-BEC")
      (libsource (lib "eagle-import") (part "-NPN-SOT23-BECBCW81"))
    )
    (comp (ref "T2")
      (value "BC807-16-PNP-SOT23-BEC")
      (footprint "eagle-import:SOT23-BEC")
      (libsource (lib "eagle-import") (part "-PNP-SOT23-BECBC807-16"))
    )
    (comp (ref "T3")
      (value "BC807-16-PNP-SOT23-BEC")
      (footprint "eagle-import:SOT23-BEC")
      (libsource (lib "eagle-import") (part "-PNP-SOT23-BECBC807-16"))
    )
    (comp (ref "U$32")
      (value "CR1220_POZ")
      (footprint "eagle-import:CR1220_POZ")
      (libsource (lib "eagle-import") (part "CR1220_POZ"))
    )
    (comp (ref "U$40")
      (value "BAS40W-04")
      (footprint "eagle-import:SOT65P210X110-3N")
      (libsource (lib "eagle-import") (part "BAS40W-04"))
    )
    (comp (ref "U1")
      (value "MCP1826S-5002E/DB")
      (footprint "eagle-import:SOT230P700X180-4N")
      (fields (field (name "MF") "Microchip"))
      (libsource (lib "eagle-import") (part "MCP1826S-5002E/DB"))
    )
    (comp (ref "U2")
      (value "MCP1826S-5002E/DB")
      (footprint "eagle-import:SOT230P700X180-4N")
      (fields (field (name "MF") "Microchip"))
      (libsource (lib "eagle-import") (part "MCP1826S-5002E/DB"))
    )
  )
  (nets
    (net (code "1") (name "+3V3") (class "Default")
      (node (ref "C10") (pin "1") (pinfunction "1_1") (pintype "passive"))
      (node (ref "C20") (pin "1") (pinfunction "1_1") (pintype "passive"))
      (node (ref "C21") (pin "1") (pinfunction "1_1") (pintype "passive"))
      (node (ref "C22") (pin "1") (pinfunction "1_1") (pintype "passive"))
      (node (ref "C23") (pin "1") (pinfunction "1_1") (pintype "passive"))
      (node (ref "C24") (pin "1") (pinfunction "1_1") (pintype "passive"))
      (node (ref "C26") (pin "1") (pinfunction "1_1") (pintype "passive"))
      (node (ref "C28") (pin "1") (pinfunction "1_1") (pintype "passive"))
      (node (ref "C3") (pin "1") (pinfunction "1_1") (pintype "passive"))
      (node (ref "C4") (pin "1") (pinfunction "1_1") (pintype "passive"))
      (node (ref "C41") (pin "1") (pinfunction "1_1") (pintype "passive"))
      (node (ref "C46") (pin "1") (pinfunction "1_1") (pintype "passive"))
      (node (ref "C47") (pin "1") (pinfunction "1_1") (pintype "passive"))
      (node (ref "C52") (pin "1") (pinfunction "1_1") (pintype "passive"))
      (node (ref "C53") (pin "1") (pinfunction "1_1") (pintype "passive"))
      (node (ref "C58") (pin "1") (pinfunction "1_1") (pintype "passive"))
      (node (ref "C71") (pin "1") (pinfunction "1_1") (pintype "passive"))
      (node (ref "C72") (pin "1") (pinfunction "1_1") (pintype "passive"))
      (node (ref "C9") (pin "1") (pinfunction "1_1") (pintype "passive"))
      (node (ref "D2") (pin "1") (pinfunction "1_1") (pintype "passive"))
      (node (ref "LED1") (pin "2") (pinfunction "A_2") (pintype "passive"))
      (node (ref "R1") (pin "1") (pinfunction "1_1") (pintype "passive"))
      (node (ref "U$31") (pin "P$1") (pinfunction "VDD_P$1") (pintype "bidirectional"))
      (node (ref "U$39") (pin "2") (pinfunction "VCC_2") (pintype "bidirectional"))
      (node (ref "U$40") (pin "2") (pinfunction "P$2_2") (pintype "bidirectional"))
      (node (ref "U$5") (pin "1") (pinfunction "1_1") (pintype "passive"))
      (node (ref "U$6") (pin "1") (pinfunction "VDD_1") (pintype "power_in"))
      (node (ref "U1") (pin "3") (pinfunction "VOUT_3") (pintype "output"))
      (node (ref "U11") (pin "1") (pinfunction "RESV_1") (pintype "bidirectional"))
      (node (ref "U11") (pin "13") (pinfunction "VDD_13") (pintype "bidirectional"))
      (node (ref "U11") (pin "8") (pinfunction "VDDIO_8") (pintype "bidirectional"))
      (node (ref "U12") (pin "19") (pinfunction "DVDD_19") (pintype "power_in"))
      (node (ref "U12") (pin "20") (pinfunction "VDD_20") (pintype "power_in"))
      (node (ref "U3") (pin "3") (pinfunction "VCC_3") (pintype "power_in"))
      (node (ref "U4") (pin "VDDA/VREF+") (pinfunction "VDDA/VREF+_VDDA/VREF+") (pintype "power_in"))
      (node (ref "U4") (pin "VDD_1") (pinfunction "VDD_1_VDD_1") (pintype "power_in"))
      (node (ref "U4") (pin "VDD_2") (pinfunction "VDD_2_VDD_2") (pintype "power_in"))
      (node (ref "U4") (pin "VDD_3") (pinfunction "VDD_3_VDD_3") (pintype "power_in"))
      (node (ref "U4") (pin "VDD_4") (pinfunction "VDD_4_VDD_4") (pintype "power_in"))
      (node (ref "U8") (pin "3") (pinfunction "VCC_3") (pintype "power_in"))
      (node (ref "U9") (pin "24") (pinfunction "DVDD_24") (pintype "power_in"))
    )
    (net (code "2") (name "+5V") (class "Default")
      (node (ref "C31") (pin "2") (pinfunction "2_2") (pintype "passive"))
      (node (ref "C33") (pin "2") (pinfunction "2_2") (pintype "passive"))
      (node (ref "C42") (pin "2") (pinfunction "2_2") (pintype "passive"))
      (node (ref "C43") (pin "+") (pinfunction "+_+") (pintype "passive"))
      (node (ref "C44") (pin "1") (pinfunction "1_1") (pintype "passive"))
      (node (ref "C45") (pin "2") (pinfunction "2_2") (pintype "passive"))
      (node (ref "C57") (pin "2") (pinfunction "2_2") (pintype "passive"))
      (node (ref "C7") (pin "1") (pinfunction "1_1") (pintype "passive"))
      (node (ref "C8") (pin "1") (pinfunction "1_1") (pintype "passive"))
      (node (ref "J3") (pin "3") (pinfunction "S_3") (pintype "passive"))
      (node (ref "R2") (pin "1") (pinfunction "1_1") (pintype "passive"))
      (node (ref "U10") (pin "8") (pinfunction "+VS_8") (pintype "power_in"))
      (node (ref "U2") (pin "3") (pinfunction "VOUT_3") (pintype "output"))
      (node (ref "U5") (pin "8") (pinfunction "+VS_8") (pintype "power_in"))
      (node (ref "U6") (pin "8") (pinfunction "+VS_8") (pintype "power_in"))
      (node (ref "U9") (pin "17") (pinfunction "REFIN1(+)_17") (pintype "input"))
      (node (ref "U9") (pin "23") (pinfunction "AVDD_23") (pintype "power_in"))
    )
    (net (code "3") (name "3V8") (class "Default")
      (node (ref "C1") (pin "1") (pinfunction "1_1") (pintype "passive"))
      (node (ref "C2") (pin "1") (pinfunction "1_1") (pintype "passive"))
      (node (ref "U$3") (pin "2") (pinfunction "2_2") (pintype "bidirectional"))
      (node (ref "U$3") (pin "4") (pinfunction "4_4") (pintype "bidirectional"))
      (node (ref "U$3") (pin "6") (pinfunction "6_6") (pintype "bidirectional"))
      (node (ref "U$4") (pin "1") (pinfunction "1_1") (pintype "bidirectional"))
      (node (ref "U$4") (pin "3") (pinfunction "3_3") (pintype "bidirectional"))
      (node (ref "U$4") (pin "5") (pinfunction "5_5") (pintype "bidirectional"))
      (node (ref "U1") (pin "1") (pinfunction "VIN_1") (pintype "input"))
    )
    (net (code "4") (name "5V5") (class "Default")
      (node (ref "C5") (pin "1") (pinfunction "1_1") (pintype "passive"))
      (node (ref "C6") (pin "1") (pinfunction "1_1") (pintype "passive"))
      (node (ref "U$3") (pin "10") (pinfunction "10_10") (pintype "bidirectional"))
      (node (ref "U$3") (pin "12") (pinfunction "12_12") (pintype "bidirectional"))
      (node (ref "U$3") (pin "8") (pinfunction "8_8") (pintype "bidirectional"))
      (node (ref "U$4") (pin "11") (pinfunction "11_11") (pintype "bidirectional"))
      (node (ref "U$4") (pin "7") (pinfunction "7_7") (pintype "bidirectional"))
      (node (ref "U$4") (pin "9") (pinfunction "9_9") (pintype "bidirectional"))
      (node (ref "U2") (pin "1") (pinfunction "VIN_1") (pintype "input"))
    )
    (net (code "5") (name "6V6") (class "Default")
      (node (ref "U$3") (pin "14") (pinfunction "14_14") (pintype "bidirectional"))
      (node (ref "U$3") (pin "16") (pinfunction "16_16") (pintype "bidirectional"))
      (node (ref "U$4") (pin "13") (pinfunction "13_13") (pintype "bidirectional"))
      (node (ref "U$4") (pin "15") (pinfunction "15_15") (pintype "bidirectional"))
    )
    (net (code "6") (name "7V4") (class "Default")
      (node (ref "U$3") (pin "1") (pinfunction "1_1") (pintype "bidirectional"))
      (node (ref "U$3") (pin "3") (pinfunction "3_3") (pintype "bidirectional"))
      (node (ref "U$3") (pin "5") (pinfunction "5_5") (pintype "bidirectional"))
      (node (ref "U$4") (pin "2") (pinfunction "2_2") (pintype "bidirectional"))
      (node (ref "U$4") (pin "4") (pinfunction "4_4") (pintype "bidirectional"))
      (node (ref "U$4") (pin "6") (pinfunction "6_6") (pintype "bidirectional"))
    )
    (net (code "7") (name "ADC_CS") (class "Default")
      (node (ref "U4") (pin "PA15") (pinfunction "PA15_PA15") (pintype "bidirectional"))
      (node (ref "U9") (pin "32") (pinfunction "~{CS}_32") (pintype "input"))
    )
    (net (code "8") (name "ADC_MISO") (class "Default")
      (node (ref "U4") (pin "PC11") (pinfunction "PC11_PC11") (pintype "bidirectional"))
      (node (ref "U9") (pin "27") (pinfunction "DOUT/~{RDY}_27") (pintype "bidirectional"))
    )
    (net (code "9") (name "ADC_MOSI") (class "Default")
      (node (ref "U4") (pin "PC12") (pinfunction "PC12_PC12") (pintype "bidirectional"))
      (node (ref "U9") (pin "28") (pinfunction "DIN_28") (pintype "input"))
    )
    (net (code "10") (name "ADC_POWER1_CURRENT") (class "Default")
      (node (ref "C65") (pin "1") (pinfunction "1_1") (pintype "passive"))
      (node (ref "R46") (pin "2") (pinfunction "2_2") (pintype "passive"))
      (node (ref "R50") (pin "1") (pinfunction "1_1") (pintype "passive"))
      (node (ref "U4") (pin "PC3") (pinfunction "PC3_PC3") (pintype "bidirectional"))
    )
    (net (code "11") (name "ADC_POWER2_CURRENT") (class "Default")
      (node (ref "C66") (pin "1") (pinfunction "1_1") (pintype "passive"))
      (node (ref "R47") (pin "2") (pinfunction "2_2") (pintype "passive"))
      (node (ref "R51") (pin "1") (pinfunction "1_1") (pintype "passive"))
      (node (ref "U4") (pin "PC2") (pinfunction "PC2_PC2") (pintype "bidirectional"))
    )
    (net (code "12") (name "ADC_POWER3_CURRENT") (class "Default")
      (node (ref "C67") (pin "1") (pinfunction "1_1") (pintype "passive"))
      (node (ref "R48") (pin "2") (pinfunction "2_2") (pintype "passive"))
      (node (ref "R52") (pin "1") (pinfunction "1_1") (pintype "passive"))
      (node (ref "U4") (pin "PC1") (pinfunction "PC1_PC1") (pintype "bidirectional"))
    )
    (net (code "13") (name "ADC_POWER4_CURRENT") (class "Default")
      (node (ref "C68") (pin "1") (pinfunction "1_1") (pintype "passive"))
      (node (ref "R49") (pin "2") (pinfunction "2_2") (pintype "passive"))
      (node (ref "R53") (pin "1") (pinfunction "1_1") (pintype "passive"))
      (node (ref "U4") (pin "PC0") (pinfunction "PC0_PC0") (pintype "bidirectional"))
    )
    (net (code "14") (name "ADC_SCLK") (class "Default")
      (node (ref "U4") (pin "PC10") (pinfunction "PC10_PC10") (pintype "bidirectional"))
      (node (ref "U9") (pin "31") (pinfunction "SCLK_31") (pintype "input"))
    )
    (net (code "15") (name "ADC_SYNC") (class "Default")
      (node (ref "U4") (pin "PD2") (pinfunction "PD2_PD2") (pintype "bidirectional"))
      (node (ref "U9") (pin "25") (pinfunction "~{SYNC}_25") (pintype "input"))
    )
    (net (code "16") (name "AGND") (class "Default")
      (node (ref "C15") (pin "1") (pinfunction "1_1") (pintype "passive"))
      (node (ref "C17") (pin "1") (pinfunction "1_1") (pintype "passive"))
      (node (ref "C18") (pin "2") (pinfunction "2_2") (pintype "passive"))
      (node (ref "C29") (pin "2") (pinfunction "2_2") (pintype "passive"))
      (node (ref "C30") (pin "2") (pinfunction "2_2") (pintype "passive"))
      (node (ref "C31") (pin "1") (pinfunction "1_1") (pintype "passive"))
      (node (ref "C32") (pin "2") (pinfunction "2_2") (pintype "passive"))
      (node (ref "C33") (pin "1") (pinfunction "1_1") (pintype "passive"))
      (node (ref "C42") (pin "1") (pinfunction "1_1") (pintype "passive"))
      (node (ref "C43") (pin "-") (pinfunction "-_-") (pintype "passive"))
      (node (ref "C44") (pin "2") (pinfunction "2_2") (pintype "passive"))
      (node (ref "C45") (pin "1") (pinfunction "1_1") (pintype "passive"))
      (node (ref "C54") (pin "1") (pinfunction "1_1") (pintype "passive"))
      (node (ref "C55") (pin "2") (pinfunction "2_2") (pintype "passive"))
      (node (ref "C56") (pin "2") (pinfunction "2_2") (pintype "passive"))
      (node (ref "C57") (pin "1") (pinfunction "1_1") (pintype "passive"))
      (node (ref "C72") (pin "2") (pinfunction "2_2") (pintype "passive"))
      (node (ref "J3") (pin "4") (pinfunction "S_4") (pintype "passive"))
      (node (ref "R11") (pin "1") (pinfunction "1_1") (pintype "passive"))
      (node (ref "R15") (pin "2") (pinfunction "2_2") (pintype "passive"))
      (node (ref "R16") (pin "1") (pinfunction "1_1") (pintype "passive"))
      (node (ref "R21") (pin "2") (pinfunction "2_2") (pintype "passive"))
      (node (ref "R57") (pin "1") (pinfunction "1_1") (pintype "passive"))
      (node (ref "R58") (pin "2") (pinfunction "2_2") (pintype "passive"))
      (node (ref "U10") (pin "5") (pinfunction "-VS_5") (pintype "power_in"))
      (node (ref "U10") (pin "6") (pinfunction "REF_6") (pintype "input"))
      (node (ref "U12") (pin "10") (pinfunction "AGND_10") (pintype "power_in"))
      (node (ref "U12") (pin "15") (pinfunction "GND_15") (pintype "power_in"))
      (node (ref "U12") (pin "16") (pinfunction "ANGD_16") (pintype "power_in"))
      (node (ref "U12") (pin "PAD") (pinfunction "PAD_PAD") (pintype "power_in"))
      (node (ref "U5") (pin "5") (pinfunction "-VS_5") (pintype "power_in"))
      (node (ref "U5") (pin "6") (pinfunction "REF_6") (pintype "input"))
      (node (ref "U6") (pin "5") (pinfunction "-VS_5") (pintype "power_in"))
      (node (ref "U6") (pin "6") (pinfunction "REF_6") (pintype "input"))
      (node (ref "U9") (pin "18") (pinfunction "REFIN1(-)_18") (pintype "input"))
      (node (ref "U9") (pin "21") (pinfunction "AGND_2_21") (pintype "passive"))
      (node (ref "U9") (pin "22") (pinfunction "DGND_22") (pintype "passive"))
      (node (ref "U9") (pin "33") (pinfunction "EP_33") (pintype "passive"))
      (node (ref "U9") (pin "5") (pinfunction "AINCOM_5") (pintype "input"))
      (node (ref "U9") (pin "6") (pinfunction "AGND_6") (pintype "passive"))
    )
    (net (code "17") (name "BACKUP_SUPPLY") (class "Default")
      (node (ref "U$1") (pin "16") (pinfunction "16_16") (pintype "bidirectional"))
      (node (ref "U$1") (pin "18") (pinfunction "18_18") (pintype "bidirectional"))
      (node (ref "U$1") (pin "20") (pinfunction "20_20") (pintype "bidirectional"))
      (node (ref "U$2") (pin "15") (pinfunction "15_15") (pintype "bidirectional"))
      (node (ref "U$2") (pin "17") (pinfunction "17_17") (pintype "bidirectional"))
      (node (ref "U$2") (pin "19") (pinfunction "19_19") (pintype "bidirectional"))
    )
    (net (code "18") (name "BURNOUT_PIN_IN") (class "Default")
      (node (ref "C49") (pin "1") (pinfunction "1_1") (pintype "passive"))
      (node (ref "R40") (pin "2") (pinfunction "2_2") (pintype "passive"))
      (node (ref "U$40") (pin "3") (pinfunction "P$3_3") (pintype "bidirectional"))
      (node (ref "U4") (pin "PC15-OSC32_OUT") (pinfunction "PC15-OSC32_OUT_PC15-OSC32_OUT") (pintype "bidirectional"))
    )
    (net (code "19") (name "BURNOUT_PIN_OUT") (class "Default")
      (node (ref "R28") (pin "2") (pinfunction "2_2") (pintype "passive"))
      (node (ref "U4") (pin "PC14-OSC32_IN") (pinfunction "PC14-OSC32_IN_PC14-OSC32_IN") (pintype "bidirectional"))
    )
    (net (code "20") (name "BUZZER") (class "Default")
      (node (ref "R27") (pin "2") (pinfunction "2_2") (pintype "passive"))
      (node (ref "U4") (pin "PA1") (pinfunction "PA1_PA1") (pintype "bidirectional"))
    )
    (net (code "21") (name "CAN2_RX") (class "Default")
      (node (ref "U4") (pin "PB12") (pinfunction "PB12_PB12") (pintype "bidirectional"))
      (node (ref "U8") (pin "4") (pinfunction "R_4") (pintype "output"))
    )
    (net (code "22") (name "CAN2_TX") (class "Default")
      (node (ref "U4") (pin "PB13") (pinfunction "PB13_PB13") (pintype "bidirectional"))
      (node (ref "U8") (pin "1") (pinfunction "D_1") (pintype "input"))
    )
    (net (code "23") (name "CANH") (class "Default")
      (node (ref "C12") (pin "1") (pinfunction "1_1") (pintype "passive"))
      (node (ref "U$1") (pin "1") (pinfunction "1_1") (pintype "bidirectional"))
      (node (ref "U$2") (pin "2") (pinfunction "2_2") (pintype "bidirectional"))
      (node (ref "U3") (pin "7") (pinfunction "CANH_7") (pintype "output"))
    )
    (net (code "24") (name "CANH2") (class "Default")
      (node (ref "C40") (pin "1") (pinfunction "1_1") (pintype "passive"))
      (node (ref "U$1") (pin "2") (pinfunction "2_2") (pintype "bidirectional"))
      (node (ref "U$2") (pin "1") (pinfunction "1_1") (pintype "bidirectional"))
      (node (ref "U8") (pin "7") (pinfunction "CANH_7") (pintype "output"))
    )
    (net (code "25") (name "CANL") (class "Default")
      (node (ref "C11") (pin "1") (pinfunction "1_1") (pintype "passive"))
      (node (ref "U$1") (pin "3") (pinfunction "3_3") (pintype "bidirectional"))
      (node (ref "U$2") (pin "4") (pinfunction "4_4") (pintype "bidirectional"))
      (node (ref "U3") (pin "6") (pinfunction "CANL_6") (pintype "output"))
    )
    (net (code "26") (name "CANL2") (class "Default")
      (node (ref "C39") (pin "1") (pinfunction "1_1") (pintype "passive"))
      (node (ref "U$1") (pin "4") (pinfunction "4_4") (pintype "bidirectional"))
      (node (ref "U$2") (pin "3") (pinfunction "3_3") (pintype "bidirectional"))
      (node (ref "U8") (pin "6") (pinfunction "CANL_6") (pintype "output"))
    )
    (net (code "27") (name "CAN_RX") (class "Default")
      (node (ref "U3") (pin "4") (pinfunction "R_4") (pintype "output"))
      (node (ref "U4") (pin "PA11") (pinfunction "PA11_PA11") (pintype "bidirectional"))
    )
    (net (code "28") (name "CAN_TX") (class "Default")
      (node (ref "U3") (pin "1") (pinfunction "D_1") (pintype "input"))
      (node (ref "U4") (pin "PA12") (pinfunction "PA12_PA12") (pintype "bidirectional"))
    )
    (net (code "29") (name "COM_BLUE") (class "Default")
      (node (ref "R108") (pin "2") (pinfunction "2_2") (pintype "passive"))
      (node (ref "U4") (pin "PB4") (pinfunction "PB4_PB4") (pintype "bidirectional"))
    )
    (net (code "30") (name "COM_GREEN") (class "Default")
      (node (ref "R107") (pin "2") (pinfunction "2_2") (pintype "passive"))
      (node (ref "U4") (pin "PB5") (pinfunction "PB5_PB5") (pintype "bidirectional"))
    )
    (net (code "31") (name "COM_RED") (class "Default")
      (node (ref "R106") (pin "2") (pinfunction "2_2") (pintype "passive"))
      (node (ref "U4") (pin "PB3") (pinfunction "PB3_PB3") (pintype "bidirectional"))
    )
    (net (code "32") (name "ENGINE_BURNOUT1") (class "Default")
      (node (ref "J1") (pin "4") (pinfunction "4_4") (pintype "bidirectional"))
      (node (ref "J2") (pin "3") (pinfunction "3_3") (pintype "bidirectional"))
      (node (ref "T3") (pin "C") (pinfunction "C_C") (pintype "passive"))
    )
    (net (code "33") (name "ENGINE_BURNOUT2") (class "Default")
      (node (ref "J1") (pin "2") (pinfunction "2_2") (pintype "bidirectional"))
      (node (ref "J2") (pin "1") (pinfunction "1_1") (pintype "bidirectional"))
      (node (ref "R38") (pin "1") (pinfunction "1_1") (pintype "passive"))
    )
    (net (code "34") (name "FLASH_CS") (class "Default")
      (node (ref "R36") (pin "2") (pinfunction "2_2") (pintype "passive"))
      (node (ref "U12") (pin "13") (pinfunction "CS_13") (pintype "input"))
      (node (ref "U4") (pin "PC6") (pinfunction "PC6_PC6") (pintype "bidirectional"))
    )
    (net (code "35") (name "FLASH_MISO") (class "Default")
      (node (ref "R35") (pin "2") (pinfunction "2_2") (pintype "passive"))
      (node (ref "U12") (pin "14") (pinfunction "SDO_14") (pintype "output"))
      (node (ref "U4") (pin "PB14") (pinfunction "PB14_PB14") (pintype "bidirectional"))
    )
    (net (code "36") (name "FLASH_MOSI") (class "Default")
      (node (ref "R34") (pin "2") (pinfunction "2_2") (pintype "passive"))
      (node (ref "U12") (pin "11") (pinfunction "SDI_11") (pintype "input"))
      (node (ref "U4") (pin "PB15") (pinfunction "PB15_PB15") (pintype "bidirectional"))
    )
    (net (code "37") (name "FLASH_RESET") (class "Default")
      (node (ref "R37") (pin "1") (pinfunction "1_1") (pintype "passive"))
      (node (ref "U4") (pin "PC8") (pinfunction "PC8_PC8") (pintype "bidirectional"))
    )
    (net (code "38") (name "FLASH_SCK") (class "Default")
      (node (ref "R33") (pin "2") (pinfunction "2_2") (pintype "passive"))
      (node (ref "U12") (pin "12") (pinfunction "SCLK_12") (pintype "input"))
      (node (ref "U4") (pin "PC7") (pinfunction "PC7_PC7") (pintype "bidirectional"))
    )
    (net (code "39") (name "GND") (class "Default")
      (node (ref "3V3") (pin "C") (pinfunction "C_C") (pintype "passive"))
      (node (ref "5V") (pin "C") (pinfunction "C_C") (pintype "passive"))
      (node (ref "BUZ2") (pin "-") (pinfunction "-_-") (pintype "bidirectional"))
      (node (ref "C1") (pin "2") (pinfunction "2_2") (pintype "passive"))
      (node (ref "C10") (pin "2") (pinfunction "2_2") (pintype "passive"))
      (node (ref "C11") (pin "2") (pinfunction "2_2") (pintype "passive"))
      (node (ref "C12") (pin "2") (pinfunction "2_2") (pintype "passive"))
      (node (ref "C13") (pin "2") (pinfunction "2_2") (pintype "passive"))
      (node (ref "C19") (pin "2") (pinfunction "2_2") (pintype "passive"))
      (node (ref "C2") (pin "2") (pinfunction "2_2") (pintype "passive"))
      (node (ref "C20") (pin "2") (pinfunction "2_2") (pintype "passive"))
      (node (ref "C21") (pin "2") (pinfunction "2_2") (pintype "passive"))
      (node (ref "C22") (pin "2") (pinfunction "2_2") (pintype "passive"))
      (node (ref "C23") (pin "2") (pinfunction "2_2") (pintype "passive"))
      (node (ref "C24") (pin "2") (pinfunction "2_2") (pintype "passive"))
      (node (ref "C25") (pin "2") (pinfunction "2_2") (pintype "passive"))
      (node (ref "C26") (pin "2") (pinfunction "2_2") (pintype "passive"))
      (node (ref "C27") (pin "2") (pinfunction "2_2") (pintype "passive"))
      (node (ref "C28") (pin "2") (pinfunction "2_2") (pintype "passive"))
      (node (ref "C3") (pin "2") (pinfunction "2_2") (pintype "passive"))
      (node (ref "C34") (pin "2") (pinfunction "2_2") (pintype "passive"))
      (node (ref "C35") (pin "2") (pinfunction "2_2") (pintype "passive"))
      (node (ref "C36") (pin "2") (pinfunction "2_2") (pintype "passive"))
      (node (ref "C37") (pin "2") (pinfunction "2_2") (pintype "passive"))
      (node (ref "C39") (pin "2") (pinfunction "2_2") (pintype "passive"))
      (node (ref "C4") (pin "2") (pinfunction "2_2") (pintype "passive"))
      (node (ref "C40") (pin "2") (pinfunction "2_2") (pintype "passive"))
      (node (ref "C41") (pin "2") (pinfunction "2_2") (pintype "passive"))
      (node (ref "C46") (pin "2") (pinfunction "2_2") (pintype "passive"))
      (node (ref "C47") (pin "2") (pinfunction "2_2") (pintype "passive"))
      (node (ref "C48") (pin "2") (pinfunction "2_2") (pintype "passive"))
      (node (ref "C49") (pin "2") (pinfunction "2_2") (pintype "passive"))
      (node (ref "C5") (pin "2") (pinfunction "2_2") (pintype "passive"))
      (node (ref "C51") (pin "2") (pinfunction "2_2") (pintype "passive"))
      (node (ref "C52") (pin "2") (pinfunction "2_2") (pintype "passive"))
      (node (ref "C53") (pin "2") (pinfunction "2_2") (pintype "passive"))
      (node (ref "C58") (pin "2") (pinfunction "2_2") (pintype "passive"))
      (node (ref "C6") (pin "2") (pinfunction "2_2") (pintype "passive"))
      (node (ref "C7") (pin "2") (pinfunction "2_2") (pintype "passive"))
      (node (ref "C71") (pin "2") (pinfunction "2_2") (pintype "passive"))
      (node (ref "C8") (pin "2") (pinfunction "2_2") (pintype "passive"))
      (node (ref "C9") (pin "2") (pinfunction "2_2") (pintype "passive"))
      (node (ref "IC1") (pin "2") (pinfunction "GND_2") (pintype "passive"))
      (node (ref "IC1") (pin "4") (pinfunction "GND_4") (pintype "passive"))
      (node (ref "IND") (pin "C") (pinfunction "C_C") (pintype "passive"))
      (node (ref "J1") (pin "9") (pinfunction "9_9") (pintype "bidirectional"))
      (node (ref "J2") (pin "10") (pinfunction "10_10") (pintype "bidirectional"))
      (node (ref "LED3") (pin "C") (pinfunction "C_C") (pintype "passive"))
      (node (ref "LED4") (pin "C") (pinfunction "C_C") (pintype "passive"))
      (node (ref "LOOP") (pin "C") (pinfunction "C_C") (pintype "passive"))
      (node (ref "R39") (pin "2") (pinfunction "2_2") (pintype "passive"))
      (node (ref "R5") (pin "1") (pinfunction "1_1") (pintype "passive"))
      (node (ref "R57") (pin "2") (pinfunction "2_2") (pintype "passive"))
      (node (ref "S1") (pin "2") (pinfunction "3_2") (pintype "passive"))
      (node (ref "S1") (pin "3") (pinfunction "3_3") (pintype "passive"))
      (node (ref "S1") (pin "5") (pinfunction "5_5") (pintype "passive"))
      (node (ref "S2") (pin "2") (pinfunction "3_2") (pintype "passive"))
      (node (ref "S2") (pin "3") (pinfunction "3_3") (pintype "passive"))
      (node (ref "S2") (pin "5") (pinfunction "5_5") (pintype "passive"))
      (node (ref "T1") (pin "E") (pinfunction "E_E") (pintype "passive"))
      (node (ref "U$1") (pin "14") (pinfunction "14_14") (pintype "bidirectional"))
      (node (ref "U$1") (pin "6") (pinfunction "6_6") (pintype "bidirectional"))
      (node (ref "U$2") (pin "13") (pinfunction "13_13") (pintype "bidirectional"))
      (node (ref "U$2") (pin "5") (pinfunction "5_5") (pintype "bidirectional"))
      (node (ref "U$3") (pin "17") (pinfunction "17_17") (pintype "bidirectional"))
      (node (ref "U$3") (pin "18") (pinfunction "18_18") (pintype "bidirectional"))
      (node (ref "U$3") (pin "19") (pinfunction "19_19") (pintype "bidirectional"))
      (node (ref "U$3") (pin "20") (pinfunction "20_20") (pintype "bidirectional"))
      (node (ref "U$31") (pin "P$2") (pinfunction "PS_P$2") (pintype "bidirectional"))
      (node (ref "U$31") (pin "P$3") (pinfunction "GND_P$3") (pintype "bidirectional"))
      (node (ref "U$32") (pin "GND") (pinfunction "-_GND") (pintype "bidirectional"))
      (node (ref "U$39") (pin "10") (pinfunction "VSS_10") (pintype "bidirectional"))
      (node (ref "U$4") (pin "17") (pinfunction "17_17") (pintype "bidirectional"))
      (node (ref "U$4") (pin "18") (pinfunction "18_18") (pintype "bidirectional"))
      (node (ref "U$4") (pin "19") (pinfunction "19_19") (pintype "bidirectional"))
      (node (ref "U$4") (pin "20") (pinfunction "20_20") (pintype "bidirectional"))
      (node (ref "U$40") (pin "1") (pinfunction "P$1_1") (pintype "bidirectional"))
      (node (ref "U$5") (pin "6") (pinfunction "6_6") (pintype "passive"))
      (node (ref "U$6") (pin "10") (pinfunction "GND_10") (pintype "power_in"))
      (node (ref "U1") (pin "2") (pinfunction "GND_2") (pintype "passive"))
      (node (ref "U1") (pin "4") (pinfunction "GND2_4") (pintype "passive"))
      (node (ref "U11") (pin "18") (pinfunction "GND_18") (pintype "bidirectional"))
      (node (ref "U11") (pin "20") (pinfunction "RESV_20") (pintype "bidirectional"))
      (node (ref "U2") (pin "2") (pinfunction "GND_2") (pintype "passive"))
      (node (ref "U2") (pin "4") (pinfunction "GND2_4") (pintype "passive"))
      (node (ref "U3") (pin "2") (pinfunction "GND_2") (pintype "passive"))
      (node (ref "U3") (pin "8") (pinfunction "RS_8") (pintype "input"))
      (node (ref "U4") (pin "VSSA/VREF-") (pinfunction "VSSA/VREF-_VSSA/VREF-") (pintype "power_in"))
      (node (ref "U4") (pin "VSS_1") (pinfunction "VSS_1_VSS_1") (pintype "power_in"))
      (node (ref "U4") (pin "VSS_2") (pinfunction "VSS_2_VSS_2") (pintype "power_in"))
      (node (ref "U4") (pin "VSS_3") (pinfunction "VSS_3_VSS_3") (pintype "power_in"))
      (node (ref "U4") (pin "VSS_4") (pinfunction "VSS_4_VSS_4") (pintype "power_in"))
      (node (ref "U8") (pin "2") (pinfunction "GND_2") (pintype "passive"))
      (node (ref "U8") (pin "8") (pinfunction "RS_8") (pintype "input"))
    )
    (net (code "40") (name "GNDA") (class "Default")
      (node (ref "C59") (pin "2") (pinfunction "2_2") (pintype "passive"))
      (node (ref "C60") (pin "2") (pinfunction "2_2") (pintype "passive"))
      (node (ref "C61") (pin "2") (pinfunction "2_2") (pintype "passive"))
      (node (ref "C62") (pin "2") (pinfunction "2_2") (pintype "passive"))
      (node (ref "C63") (pin "2") (pinfunction "2_2") (pintype "passive"))
      (node (ref "C64") (pin "2") (pinfunction "2_2") (pintype "passive"))
      (node (ref "C65") (pin "2") (pinfunction "2_2") (pintype "passive"))
      (node (ref "C66") (pin "2") (pinfunction "2_2") (pintype "passive"))
      (node (ref "C67") (pin "2") (pinfunction "2_2") (pintype "passive"))
      (node (ref "C68") (pin "2") (pinfunction "2_2") (pintype "passive"))
      (node (ref "D1") (pin "C") (pinfunction "C_C") (pintype "passive"))
      (node (ref "J6") (pin "2") (pinfunction "2_2") (pintype "passive"))
      (node (ref "J7") (pin "2") (pinfunction "2_2") (pintype "passive"))
      (node (ref "R50") (pin "2") (pinfunction "2_2") (pintype "passive"))
      (node (ref "R51") (pin "2") (pinfunction "2_2") (pintype "passive"))
      (node (ref "R52") (pin "2") (pinfunction "2_2") (pintype "passive"))
      (node (ref "R53") (pin "2") (pinfunction "2_2") (pintype "passive"))
      (node (ref "R54") (pin "1") (pinfunction "1_1") (pintype "passive"))
      (node (ref "R58") (pin "1") (pinfunction "1_1") (pintype "passive"))
      (node (ref "U$1") (pin "11") (pinfunction "11_11") (pintype "bidirectional"))
      (node (ref "U$2") (pin "12") (pinfunction "12_12") (pintype "bidirectional"))
    )
    (net (code "41") (name "IND_LED") (class "Default")
      (node (ref "R7") (pin "1") (pinfunction "1_1") (pintype "passive"))
      (node (ref "U4") (pin "PB2") (pinfunction "PB2_PB2") (pintype "bidirectional"))
    )
    (net (code "42") (name "LED_GREEN") (class "Default")
      (node (ref "R6") (pin "2") (pinfunction "2_2") (pintype "passive"))
      (node (ref "U4") (pin "PC9") (pinfunction "PC9_PC9") (pintype "bidirectional"))
    )
    (net (code "43") (name "LED_RED") (class "Default")
      (node (ref "R4") (pin "2") (pinfunction "2_2") (pintype "passive"))
      (node (ref "U4") (pin "PA8") (pinfunction "PA8_PA8") (pintype "bidirectional"))
    )
    (net (code "44") (name "LINE4") (class "Default")
      (node (ref "U$1") (pin "5") (pinfunction "5_5") (pintype "bidirectional"))
      (node (ref "U$2") (pin "6") (pinfunction "6_6") (pintype "bidirectional"))
    )
    (net (code "45") (name "LINE5") (class "Default")
      (node (ref "U$1") (pin "7") (pinfunction "7_7") (pintype "bidirectional"))
      (node (ref "U$2") (pin "8") (pinfunction "8_8") (pintype "bidirectional"))
    )
    (net (code "46") (name "LOOP_LED") (class "Default")
      (node (ref "R3") (pin "1") (pinfunction "1_1") (pintype "passive"))
      (node (ref "U4") (pin "PB10") (pinfunction "PB10_PB10") (pintype "bidirectional"))
    )
    (net (code "47") (name "MAX_DRDY") (class "Default")
      (node (ref "U12") (pin "18") (pinfunction "DRDY_18") (pintype "output"))
      (node (ref "U4") (pin "PA0") (pinfunction "PA0_PA0") (pintype "bidirectional"))
    )
    (net (code "48") (name "MAX_FORCE+") (class "Default")
      (node (ref "J1") (pin "6") (pinfunction "6_6") (pintype "bidirectional"))
      (node (ref "J2") (pin "5") (pinfunction "5_5") (pintype "bidirectional"))
      (node (ref "U12") (pin "5") (pinfunction "FORCE+_5") (pintype "output"))
      (node (ref "U12") (pin "6") (pinfunction "FORCE2_6") (pintype "bidirectional"))
    )
    (net (code "49") (name "MAX_RTDIN+") (class "Default")
      (node (ref "C73") (pin "1") (pinfunction "1_1") (pintype "passive"))
      (node (ref "J1") (pin "1") (pinfunction "1_1") (pintype "bidirectional"))
      (node (ref "J2") (pin "2") (pinfunction "2_2") (pintype "bidirectional"))
      (node (ref "U12") (pin "7") (pinfunction "RTDIN+_7") (pintype "bidirectional"))
    )
    (net (code "50") (name "MAX_RTDIN-") (class "Default")
      (node (ref "C73") (pin "2") (pinfunction "2_2") (pintype "passive"))
      (node (ref "J1") (pin "3") (pinfunction "3_3") (pintype "bidirectional"))
      (node (ref "J2") (pin "4") (pinfunction "4_4") (pintype "bidirectional"))
      (node (ref "U12") (pin "8") (pinfunction "RTDIN-_8") (pintype "bidirectional"))
      (node (ref "U12") (pin "9") (pinfunction "FORCE-_9") (pintype "input"))
    )
    (net (code "51") (name "MPU_CS") (class "Default")
      (node (ref "U11") (pin "22") (pinfunction "NCS_22") (pintype "bidirectional"))
      (node (ref "U4") (pin "PC4") (pinfunction "PC4_PC4") (pintype "bidirectional"))
    )
    (net (code "52") (name "MPU_INT") (class "Default")
      (node (ref "U11") (pin "12") (pinfunction "INT_12") (pintype "bidirectional"))
      (node (ref "U4") (pin "PC5") (pinfunction "PC5_PC5") (pintype "bidirectional"))
    )
    (net (code "53") (name "MS56_CS") (class "Default")
      (node (ref "U$31") (pin "P$4") (pinfunction "CSB_P$4") (pintype "bidirectional"))
      (node (ref "U$31") (pin "P$5") (pinfunction "CSB_P$5") (pintype "bidirectional"))
      (node (ref "U4") (pin "PA4") (pinfunction "PA4_PA4") (pintype "bidirectional"))
    )
    (net (code "54") (name "NRST") (class "Default")
      (node (ref "C25") (pin "1") (pinfunction "1_1") (pintype "passive"))
      (node (ref "S2") (pin "1") (pinfunction "1_1") (pintype "passive"))
      (node (ref "S2") (pin "4") (pinfunction "1_4") (pintype "passive"))
      (node (ref "U$5") (pin "5") (pinfunction "5_5") (pintype "passive"))
      (node (ref "U4") (pin "NRST") (pinfunction "NRST_NRST") (pintype "bidirectional"))
    )
    (net (code "55") (name "Net-(3V3-PadA)") (class "Default")
      (node (ref "3V3") (pin "A") (pinfunction "A_A") (pintype "passive"))
      (node (ref "R1") (pin "2") (pinfunction "2_2") (pintype "passive"))
    )
    (net (code "56") (name "Net-(5V-PadA)") (class "Default")
      (node (ref "5V") (pin "A") (pinfunction "A_A") (pintype "passive"))
      (node (ref "R2") (pin "2") (pinfunction "2_2") (pintype "passive"))
    )
    (net (code "57") (name "Net-(BUZ2-Pad+)") (class "Default")
      (node (ref "BUZ2") (pin "+") (pinfunction "+_+") (pintype "bidirectional"))
      (node (ref "T2") (pin "C") (pinfunction "C_C") (pintype "passive"))
    )
    (net (code "58") (name "Net-(C19-Pad1)") (class "Default")
      (node (ref "C19") (pin "1") (pinfunction "1_1") (pintype "passive"))
      (node (ref "U4") (pin "VCAP_1") (pinfunction "VCAP_1_VCAP_1") (pintype "power_in"))
    )
    (net (code "59") (name "Net-(D2-Pad2)") (class "Default")
      (node (ref "D2") (pin "2") (pinfunction "2_2") (pintype "passive"))
      (node (ref "R106") (pin "1") (pinfunction "1_1") (pintype "passive"))
    )
    (net (code "60") (name "Net-(D2-Pad3)") (class "Default")
      (node (ref "D2") (pin "3") (pinfunction "3_3") (pintype "passive"))
      (node (ref "R107") (pin "1") (pinfunction "1_1") (pintype "passive"))
    )
    (net (code "61") (name "Net-(D2-Pad4)") (class "Default")
      (node (ref "D2") (pin "4") (pinfunction "4_4") (pintype "passive"))
      (node (ref "R108") (pin "1") (pinfunction "1_1") (pintype "passive"))
    )
    (net (code "62") (name "Net-(IND-PadA)") (class "Default")
      (node (ref "IND") (pin "A") (pinfunction "A_A") (pintype "passive"))
      (node (ref "R7") (pin "2") (pinfunction "2_2") (pintype "passive"))
    )
    (net (code "63") (name "Net-(LED1-CG)") (class "Default")
      (node (ref "LED1") (pin "1") (pinfunction "CG_1") (pintype "passive"))
      (node (ref "R6") (pin "1") (pinfunction "1_1") (pintype "passive"))
    )
    (net (code "64") (name "Net-(LED1-CR)") (class "Default")
      (node (ref "LED1") (pin "3") (pinfunction "CR_3") (pintype "passive"))
      (node (ref "R4") (pin "1") (pinfunction "1_1") (pintype "passive"))
    )
    (net (code "65") (name "Net-(LED3-PadA)") (class "Default")
      (node (ref "LED3") (pin "A") (pinfunction "A_A") (pintype "passive"))
      (node (ref "R8") (pin "1") (pinfunction "1_1") (pintype "passive"))
    )
    (net (code "66") (name "Net-(LED4-PadA)") (class "Default")
      (node (ref "LED4") (pin "A") (pinfunction "A_A") (pintype "passive"))
      (node (ref "R9") (pin "2") (pinfunction "2_2") (pintype "passive"))
    )
    (net (code "67") (name "Net-(LOOP-PadA)") (class "Default")
      (node (ref "LOOP") (pin "A") (pinfunction "A_A") (pintype "passive"))
      (node (ref "R3") (pin "2") (pinfunction "2_2") (pintype "passive"))
    )
    (net (code "68") (name "Net-(R5-Pad2)") (class "Default")
      (node (ref "R5") (pin "2") (pinfunction "2_2") (pintype "passive"))
      (node (ref "U4") (pin "BOOT0") (pinfunction "BOOT0_BOOT0") (pintype "input"))
    )
    (net (code "69") (name "Net-(R25-Pad1)") (class "Default")
      (node (ref "R25") (pin "1") (pinfunction "1_1") (pintype "passive"))
      (node (ref "R26") (pin "1") (pinfunction "1_1") (pintype "passive"))
      (node (ref "T2") (pin "B") (pinfunction "B_B") (pintype "passive"))
    )
    (net (code "70") (name "Net-(R26-Pad2)") (class "Default")
      (node (ref "R26") (pin "2") (pinfunction "2_2") (pintype "passive"))
      (node (ref "T1") (pin "C") (pinfunction "C_C") (pintype "passive"))
    )
    (net (code "71") (name "Net-(R27-Pad1)") (class "Default")
      (node (ref "R27") (pin "1") (pinfunction "1_1") (pintype "passive"))
      (node (ref "T1") (pin "B") (pinfunction "B_B") (pintype "passive"))
    )
    (net (code "72") (name "Net-(R28-Pad1)") (class "Default")
      (node (ref "R28") (pin "1") (pinfunction "1_1") (pintype "passive"))
      (node (ref "T3") (pin "B") (pinfunction "B_B") (pintype "passive"))
    )
    (net (code "73") (name "Net-(R38-Pad2)") (class "Default")
      (node (ref "R38") (pin "2") (pinfunction "2_2") (pintype "passive"))
      (node (ref "R39") (pin "1") (pinfunction "1_1") (pintype "passive"))
      (node (ref "R40") (pin "1") (pinfunction "1_1") (pintype "passive"))
    )
    (net (code "74") (name "Net-(R55-Pad2)") (class "Default")
      (node (ref "R55") (pin "2") (pinfunction "2_2") (pintype "passive"))
      (node (ref "U4") (pin "PB0") (pinfunction "PB0_PB0") (pintype "bidirectional"))
    )
    (net (code "75") (name "Net-(R56-Pad2)") (class "Default")
      (node (ref "R56") (pin "2") (pinfunction "2_2") (pintype "passive"))
      (node (ref "U4") (pin "PB1") (pinfunction "PB1_PB1") (pintype "bidirectional"))
    )
    (net (code "76") (name "Net-(U$6-DIO5)") (class "Default")
      (node (ref "R9") (pin "1") (pinfunction "1_1") (pintype "passive"))
      (node (ref "U$6") (pin "15") (pinfunction "DIO5_15") (pintype "bidirectional"))
    )
    (net (code "77") (name "Net-(U$6-RESET)") (class "Default")
      (node (ref "C13") (pin "1") (pinfunction "1_1") (pintype "passive"))
      (node (ref "S1") (pin "1") (pinfunction "1_1") (pintype "passive"))
      (node (ref "S1") (pin "4") (pinfunction "1_4") (pintype "passive"))
      (node (ref "U$6") (pin "5") (pinfunction "RESET_5") (pintype "input"))
    )
    (net (code "78") (name "Net-(U$6-RSSI)") (class "Default")
      (node (ref "R8") (pin "2") (pinfunction "2_2") (pintype "passive"))
      (node (ref "U$6") (pin "6") (pinfunction "RSSI_6") (pintype "bidirectional"))
    )
    (net (code "79") (name "Net-(U$39-SCK)") (class "Default")
      (node (ref "R33") (pin "1") (pinfunction "1_1") (pintype "passive"))
      (node (ref "U$39") (pin "16") (pinfunction "SCK_16") (pintype "bidirectional"))
    )
    (net (code "80") (name "Net-(U$39-SI)") (class "Default")
      (node (ref "R34") (pin "1") (pinfunction "1_1") (pintype "passive"))
      (node (ref "U$39") (pin "15") (pinfunction "SI_15") (pintype "bidirectional"))
    )
    (net (code "81") (name "Net-(U$39-SO)") (class "Default")
      (node (ref "R35") (pin "1") (pinfunction "1_1") (pintype "passive"))
      (node (ref "U$39") (pin "8") (pinfunction "SO_8") (pintype "bidirectional"))
    )
    (net (code "82") (name "Net-(U$39-~{CS})") (class "Default")
      (node (ref "R36") (pin "1") (pinfunction "1_1") (pintype "passive"))
      (node (ref "U$39") (pin "7") (pinfunction "~{CS}_7") (pintype "bidirectional"))
    )
    (net (code "83") (name "Net-(U$39-~{RESET})") (class "Default")
      (node (ref "R37") (pin "2") (pinfunction "2_2") (pintype "passive"))
      (node (ref "U$39") (pin "3") (pinfunction "~{RESET}_3") (pintype "bidirectional"))
    )
    (net (code "84") (name "Net-(U5-+IN)") (class "Default")
      (node (ref "C14") (pin "2") (pinfunction "2_2") (pintype "passive"))
      (node (ref "C29") (pin "1") (pinfunction "1_1") (pintype "passive"))
      (node (ref "R12") (pin "2") (pinfunction "2_2") (pintype "passive"))
      (node (ref "U5") (pin "4") (pinfunction "+IN_4") (pintype "input"))
    )
    (net (code "85") (name "Net-(U5--IN)") (class "Default")
      (node (ref "C14") (pin "1") (pinfunction "1_1") (pintype "passive"))
      (node (ref "C15") (pin "2") (pinfunction "2_2") (pintype "passive"))
      (node (ref "R16") (pin "2") (pinfunction "2_2") (pintype "passive"))
      (node (ref "U5") (pin "1") (pinfunction "-IN_1") (pintype "input"))
    )
    (net (code "86") (name "Net-(U5-RG)") (class "Default")
      (node (ref "R20") (pin "1") (pinfunction "1_1") (pintype "passive"))
      (node (ref "U5") (pin "3") (pinfunction "RG_3") (pintype "passive"))
    )
    (net (code "87") (name "Net-(U5-RG_2)") (class "Default")
      (node (ref "R20") (pin "2") (pinfunction "2_2") (pintype "passive"))
      (node (ref "U5") (pin "2") (pinfunction "RG_2_2") (pintype "passive"))
    )
    (net (code "88") (name "Net-(U5-VOUT)") (class "Default")
      (node (ref "R18") (pin "1") (pinfunction "1_1") (pintype "passive"))
      (node (ref "U5") (pin "7") (pinfunction "VOUT_7") (pintype "output"))
    )
    (net (code "89") (name "Net-(U6-+IN)") (class "Default")
      (node (ref "C16") (pin "2") (pinfunction "2_2") (pintype "passive"))
      (node (ref "C18") (pin "1") (pinfunction "1_1") (pintype "passive"))
      (node (ref "R10") (pin "2") (pinfunction "2_2") (pintype "passive"))
      (node (ref "U6") (pin "4") (pinfunction "+IN_4") (pintype "input"))
    )
    (net (code "90") (name "Net-(U6--IN)") (class "Default")
      (node (ref "C16") (pin "1") (pinfunction "1_1") (pintype "passive"))
      (node (ref "C17") (pin "2") (pinfunction "2_2") (pintype "passive"))
      (node (ref "R11") (pin "2") (pinfunction "2_2") (pintype "passive"))
      (node (ref "U6") (pin "1") (pinfunction "-IN_1") (pintype "input"))
    )
    (net (code "91") (name "Net-(U6-RG)") (class "Default")
      (node (ref "R14") (pin "1") (pinfunction "1_1") (pintype "passive"))
      (node (ref "U6") (pin "3") (pinfunction "RG_3") (pintype "passive"))
    )
    (net (code "92") (name "Net-(U6-RG_2)") (class "Default")
      (node (ref "R14") (pin "2") (pinfunction "2_2") (pintype "passive"))
      (node (ref "U6") (pin "2") (pinfunction "RG_2_2") (pintype "passive"))
    )
    (net (code "93") (name "Net-(U6-VOUT)") (class "Default")
      (node (ref "R13") (pin "1") (pinfunction "1_1") (pintype "passive"))
      (node (ref "U6") (pin "7") (pinfunction "VOUT_7") (pintype "output"))
    )
    (net (code "94") (name "Net-(U10-+IN)") (class "Default")
      (node (ref "C50") (pin "2") (pinfunction "2_2") (pintype "passive"))
      (node (ref "C55") (pin "1") (pinfunction "1_1") (pintype "passive"))
      (node (ref "R29") (pin "2") (pinfunction "2_2") (pintype "passive"))
      (node (ref "U10") (pin "4") (pinfunction "+IN_4") (pintype "input"))
    )
    (net (code "95") (name "Net-(U10--IN)") (class "Default")
      (node (ref "C50") (pin "1") (pinfunction "1_1") (pintype "passive"))
      (node (ref "C54") (pin "2") (pinfunction "2_2") (pintype "passive"))
      (node (ref "R30") (pin "2") (pinfunction "2_2") (pintype "passive"))
      (node (ref "U10") (pin "1") (pinfunction "-IN_1") (pintype "input"))
    )
    (net (code "96") (name "Net-(U10-RG)") (class "Default")
      (node (ref "R32") (pin "1") (pinfunction "1_1") (pintype "passive"))
      (node (ref "U10") (pin "3") (pinfunction "RG_3") (pintype "passive"))
    )
    (net (code "97") (name "Net-(U10-RG_2)") (class "Default")
      (node (ref "R32") (pin "2") (pinfunction "2_2") (pintype "passive"))
      (node (ref "U10") (pin "2") (pinfunction "RG_2_2") (pintype "passive"))
    )
    (net (code "98") (name "Net-(U10-VOUT)") (class "Default")
      (node (ref "R31") (pin "1") (pinfunction "1_1") (pintype "passive"))
      (node (ref "U10") (pin "7") (pinfunction "VOUT_7") (pintype "output"))
    )
    (net (code "99") (name "Net-(U11-REGOUT)") (class "Default")
      (node (ref "C51") (pin "1") (pinfunction "1_1") (pintype "passive"))
      (node (ref "U11") (pin "10") (pinfunction "REGOUT_10") (pintype "bidirectional"))
    )
    (net (code "100") (name "Net-(U12-BIAS)") (class "Default")
      (node (ref "R61") (pin "2") (pinfunction "2_2") (pintype "passive"))
      (node (ref "U12") (pin "1") (pinfunction "BIAS_1") (pintype "output"))
      (node (ref "U12") (pin "2") (pinfunction "REFIN+_2") (pintype "bidirectional"))
    )
    (net (code "101") (name "Net-(U12-ISENSOR)") (class "Default")
      (node (ref "R61") (pin "1") (pinfunction "1_1") (pintype "passive"))
      (node (ref "U12") (pin "3") (pinfunction "REFIN-_3") (pintype "bidirectional"))
      (node (ref "U12") (pin "4") (pinfunction "ISENSOR_4") (pintype "input"))
    )
    (net (code "102") (name "Net-(VNQ5027AK-E1-CS_DIS)") (class "Default")
      (node (ref "R45") (pin "2") (pinfunction "2_2") (pintype "passive"))
      (node (ref "VNQ5027AK-E1") (pin "P$11") (pinfunction "CS_DIS_P$11") (pintype "bidirectional"))
    )
    (net (code "103") (name "Net-(VNQ5027AK-E1-CURRENT_SENSE1)") (class "Default")
      (node (ref "R46") (pin "1") (pinfunction "1_1") (pintype "passive"))
      (node (ref "VNQ5027AK-E1") (pin "P$4") (pinfunction "CURRENT_SENSE1_P$4") (pintype "bidirectional"))
    )
    (net (code "104") (name "Net-(VNQ5027AK-E1-CURRENT_SENSE2)") (class "Default")
      (node (ref "R47") (pin "1") (pinfunction "1_1") (pintype "passive"))
      (node (ref "VNQ5027AK-E1") (pin "P$6") (pinfunction "CURRENT_SENSE2_P$6") (pintype "bidirectional"))
    )
    (net (code "105") (name "Net-(VNQ5027AK-E1-CURRENT_SENSE3)") (class "Default")
      (node (ref "R48") (pin "1") (pinfunction "1_1") (pintype "passive"))
      (node (ref "VNQ5027AK-E1") (pin "P$8") (pinfunction "CURRENT_SENSE3_P$8") (pintype "bidirectional"))
    )
    (net (code "106") (name "Net-(VNQ5027AK-E1-CURRENT_SENSE4)") (class "Default")
      (node (ref "R49") (pin "1") (pinfunction "1_1") (pintype "passive"))
      (node (ref "VNQ5027AK-E1") (pin "P$10") (pinfunction "CURRENT_SENSE4_P$10") (pintype "bidirectional"))
    )
    (net (code "107") (name "Net-(VNQ5027AK-E1-GND)") (class "Default")
      (node (ref "D1") (pin "A") (pinfunction "A_A") (pintype "passive"))
      (node (ref "R54") (pin "2") (pinfunction "2_2") (pintype "passive"))
      (node (ref "VNQ5027AK-E1") (pin "P$2") (pinfunction "GND_P$2") (pintype "bidirectional"))
    )
    (net (code "108") (name "Net-(VNQ5027AK-E1-INPUT1)") (class "Default")
      (node (ref "R41") (pin "2") (pinfunction "2_2") (pintype "passive"))
      (node (ref "VNQ5027AK-E1") (pin "P$3") (pinfunction "INPUT1_P$3") (pintype "bidirectional"))
    )
    (net (code "109") (name "Net-(VNQ5027AK-E1-INPUT2)") (class "Default")
      (node (ref "R42") (pin "2") (pinfunction "2_2") (pintype "passive"))
      (node (ref "VNQ5027AK-E1") (pin "P$5") (pinfunction "INPUT2_P$5") (pintype "bidirectional"))
    )
    (net (code "110") (name "Net-(VNQ5027AK-E1-INPUT3)") (class "Default")
      (node (ref "R43") (pin "2") (pinfunction "2_2") (pintype "passive"))
      (node (ref "VNQ5027AK-E1") (pin "P$7") (pinfunction "INPUT3_P$7") (pintype "bidirectional"))
    )
    (net (code "111") (name "Net-(VNQ5027AK-E1-INPUT4)") (class "Default")
      (node (ref "R44") (pin "2") (pinfunction "2_2") (pintype "passive"))
      (node (ref "VNQ5027AK-E1") (pin "P$9") (pinfunction "INPUT4_P$9") (pintype "bidirectional"))
    )
    (net (code "112") (name "POWER_CS") (class "Default")
      (node (ref "R45") (pin "1") (pinfunction "1_1") (pintype "passive"))
      (node (ref "U4") (pin "PC13") (pinfunction "PC13_PC13") (pintype "bidirectional"))
    )
    (net (code "113") (name "POWER_INPUT1") (class "Default")
      (node (ref "R41") (pin "1") (pinfunction "1_1") (pintype "passive"))
      (node (ref "U4") (pin "PB9") (pinfunction "PB9_PB9") (pintype "bidirectional"))
    )
    (net (code "114") (name "POWER_INPUT2") (class "Default")
      (node (ref "R42") (pin "1") (pinfunction "1_1") (pintype "passive"))
      (node (ref "U4") (pin "PB8") (pinfunction "PB8_PB8") (pintype "bidirectional"))
    )
    (net (code "115") (name "POWER_INPUT3") (class "Default")
      (node (ref "R43") (pin "1") (pinfunction "1_1") (pintype "passive"))
      (node (ref "U4") (pin "PB7") (pinfunction "PB7_PB7") (pintype "bidirectional"))
    )
    (net (code "116") (name "POWER_INPUT4") (class "Default")
      (node (ref "R44") (pin "1") (pinfunction "1_1") (pintype "passive"))
      (node (ref "U4") (pin "PB6") (pinfunction "PB6_PB6") (pintype "bidirectional"))
    )
    (net (code "117") (name "POWER_OUTPUT1") (class "Default")
      (node (ref "C61") (pin "1") (pinfunction "1_1") (pintype "passive"))
      (node (ref "J7") (pin "1") (pinfunction "1_1") (pintype "passive"))
      (node (ref "VNQ5027AK-E1") (pin "P$13") (pinfunction "OUTPUT1_1_P$13") (pintype "bidirectional"))
      (node (ref "VNQ5027AK-E1") (pin "P$14") (pinfunction "OUTPUT1_2_P$14") (pintype "bidirectional"))
      (node (ref "VNQ5027AK-E1") (pin "P$15") (pinfunction "OUTPUT1_3_P$15") (pintype "bidirectional"))
    )
    (net (code "118") (name "POWER_OUTPUT2") (class "Default")
      (node (ref "C62") (pin "1") (pinfunction "1_1") (pintype "passive"))
      (node (ref "U$1") (pin "9") (pinfunction "9_9") (pintype "bidirectional"))
      (node (ref "U$2") (pin "10") (pinfunction "10_10") (pintype "bidirectional"))
      (node (ref "VNQ5027AK-E1") (pin "P$16") (pinfunction "OUTPUT2_1_P$16") (pintype "bidirectional"))
      (node (ref "VNQ5027AK-E1") (pin "P$17") (pinfunction "OUTPUT2_2_P$17") (pintype "bidirectional"))
      (node (ref "VNQ5027AK-E1") (pin "P$18") (pinfunction "OUTPUT2_3_P$18") (pintype "bidirectional"))
    )
    (net (code "119") (name "POWER_OUTPUT3") (class "Default")
      (node (ref "C63") (pin "1") (pinfunction "1_1") (pintype "passive"))
      (node (ref "VNQ5027AK-E1") (pin "P$19") (pinfunction "OUTPUT3_1_P$19") (pintype "bidirectional"))
      (node (ref "VNQ5027AK-E1") (pin "P$20") (pinfunction "OUTPUT3_2_P$20") (pintype "bidirectional"))
      (node (ref "VNQ5027AK-E1") (pin "P$21") (pinfunction "OUTPUT3_3_P$21") (pintype "bidirectional"))
    )
    (net (code "120") (name "POWER_OUTPUT4") (class "Default")
      (node (ref "C64") (pin "1") (pinfunction "1_1") (pintype "passive"))
      (node (ref "J6") (pin "1") (pinfunction "1_1") (pintype "passive"))
      (node (ref "VNQ5027AK-E1") (pin "P$22") (pinfunction "OUTPUT4_1_P$22") (pintype "bidirectional"))
      (node (ref "VNQ5027AK-E1") (pin "P$23") (pinfunction "OUTPUT4_2_P$23") (pintype "bidirectional"))
      (node (ref "VNQ5027AK-E1") (pin "P$24") (pinfunction "OUTPUT4_3_P$24") (pintype "bidirectional"))
    )
    (net (code "121") (name "PRESSURE1") (class "Default")
      (node (ref "C30") (pin "1") (pinfunction "1_1") (pintype "passive"))
      (node (ref "R18") (pin "2") (pinfunction "2_2") (pintype "passive"))
      (node (ref "U9") (pin "16") (pinfunction "AIN14_16") (pintype "input"))
    )
    (net (code "122") (name "PRESSURE2") (class "Default")
      (node (ref "C32") (pin "1") (pinfunction "1_1") (pintype "passive"))
      (node (ref "R13") (pin "2") (pinfunction "2_2") (pintype "passive"))
      (node (ref "U9") (pin "19") (pinfunction "AIN15_19") (pintype "input"))
    )
    (net (code "123") (name "PRESSURE_IN1+") (class "Default")
      (node (ref "J1") (pin "5") (pinfunction "5_5") (pintype "bidirectional"))
      (node (ref "J2") (pin "6") (pinfunction "6_6") (pintype "bidirectional"))
      (node (ref "R12") (pin "1") (pinfunction "1_1") (pintype "passive"))
      (node (ref "R21") (pin "1") (pinfunction "1_1") (pintype "passive"))
    )
    (net (code "124") (name "PRESSURE_IN2+") (class "Default")
      (node (ref "J1") (pin "8") (pinfunction "8_8") (pintype "bidirectional"))
      (node (ref "J2") (pin "7") (pinfunction "7_7") (pintype "bidirectional"))
      (node (ref "R10") (pin "1") (pinfunction "1_1") (pintype "passive"))
      (node (ref "R15") (pin "1") (pinfunction "1_1") (pintype "passive"))
    )
    (net (code "125") (name "PRESSURE_VCC") (class "Default")
      (node (ref "C36") (pin "1") (pinfunction "1_1") (pintype "passive"))
      (node (ref "C37") (pin "1") (pinfunction "1_1") (pintype "passive"))
      (node (ref "IC1") (pin "3") (pinfunction "VO_3") (pintype "passive"))
      (node (ref "J1") (pin "10") (pinfunction "10_10") (pintype "bidirectional"))
      (node (ref "J1") (pin "7") (pinfunction "7_7") (pintype "bidirectional"))
      (node (ref "J2") (pin "8") (pinfunction "8_8") (pintype "bidirectional"))
      (node (ref "J2") (pin "9") (pinfunction "9_9") (pintype "bidirectional"))
    )
    (net (code "126") (name "PWM1") (class "Default")
      (node (ref "R55") (pin "1") (pinfunction "1_1") (pintype "passive"))
      (node (ref "U$1") (pin "19") (pinfunction "19_19") (pintype "bidirectional"))
      (node (ref "U$2") (pin "20") (pinfunction "20_20") (pintype "bidirectional"))
    )
    (net (code "127") (name "PWM2") (class "Default")
      (node (ref "R56") (pin "1") (pinfunction "1_1") (pintype "passive"))
      (node (ref "U$1") (pin "17") (pinfunction "17_17") (pintype "bidirectional"))
      (node (ref "U$2") (pin "18") (pinfunction "18_18") (pintype "bidirectional"))
    )
    (net (code "128") (name "PWM3") (class "Default")
      (node (ref "U$1") (pin "15") (pinfunction "15_15") (pintype "bidirectional"))
      (node (ref "U$2") (pin "16") (pinfunction "16_16") (pintype "bidirectional"))
    )
    (net (code "129") (name "PWM4") (class "Default")
      (node (ref "U$1") (pin "13") (pinfunction "13_13") (pintype "bidirectional"))
      (node (ref "U$2") (pin "14") (pinfunction "14_14") (pintype "bidirectional"))
    )
    (net (code "130") (name "R_MISO") (class "Default")
      (node (ref "U$1") (pin "8") (pinfunction "8_8") (pintype "bidirectional"))
      (node (ref "U$2") (pin "7") (pinfunction "7_7") (pintype "bidirectional"))
    )
    (net (code "131") (name "R_MOSI") (class "Default")
      (node (ref "U$1") (pin "10") (pinfunction "10_10") (pintype "bidirectional"))
      (node (ref "U$2") (pin "9") (pinfunction "9_9") (pintype "bidirectional"))
    )
    (net (code "132") (name "R_SCK") (class "Default")
      (node (ref "U$1") (pin "12") (pinfunction "12_12") (pintype "bidirectional"))
      (node (ref "U$2") (pin "11") (pinfunction "11_11") (pintype "bidirectional"))
    )
    (net (code "133") (name "SENSOR_MISO") (class "Default")
      (node (ref "U$31") (pin "P$6") (pinfunction "SDO_P$6") (pintype "bidirectional"))
      (node (ref "U11") (pin "9") (pinfunction "AD0/SDO_9") (pintype "bidirectional"))
      (node (ref "U4") (pin "PA6") (pinfunction "PA6_PA6") (pintype "bidirectional"))
    )
    (net (code "134") (name "SENSOR_MOSI") (class "Default")
      (node (ref "U$31") (pin "P$7") (pinfunction "SDI/SDA_P$7") (pintype "bidirectional"))
      (node (ref "U11") (pin "24") (pinfunction "SDA/SDI_24") (pintype "bidirectional"))
      (node (ref "U4") (pin "PA7") (pinfunction "PA7_PA7") (pintype "bidirectional"))
    )
    (net (code "135") (name "SENSOR_SCLK") (class "Default")
      (node (ref "U$31") (pin "P$8") (pinfunction "SCLK_P$8") (pintype "bidirectional"))
      (node (ref "U11") (pin "23") (pinfunction "SCL/SCLK_23") (pintype "bidirectional"))
      (node (ref "U4") (pin "PA5") (pinfunction "PA5_PA5") (pintype "bidirectional"))
    )
    (net (code "136") (name "SERVO_RECO1") (class "Default")
      (node (ref "U$3") (pin "13") (pinfunction "13_13") (pintype "bidirectional"))
      (node (ref "U$4") (pin "14") (pinfunction "14_14") (pintype "bidirectional"))
    )
    (net (code "137") (name "SERVO_RECO2") (class "Default")
      (node (ref "U$3") (pin "11") (pinfunction "11_11") (pintype "bidirectional"))
      (node (ref "U$4") (pin "12") (pinfunction "12_12") (pintype "bidirectional"))
    )
    (net (code "138") (name "STLINK_RX") (class "Default")
      (node (ref "U$5") (pin "8") (pinfunction "8_8") (pintype "passive"))
      (node (ref "U4") (pin "PA3") (pinfunction "PA3_PA3") (pintype "bidirectional"))
    )
    (net (code "139") (name "STLINK_TX") (class "Default")
      (node (ref "U$5") (pin "7") (pinfunction "7_7") (pintype "passive"))
      (node (ref "U4") (pin "PA2") (pinfunction "PA2_PA2") (pintype "bidirectional"))
    )
    (net (code "140") (name "SUPPLY") (class "Default")
      (node (ref "C34") (pin "1") (pinfunction "1_1") (pintype "passive"))
      (node (ref "C35") (pin "1") (pinfunction "1_1") (pintype "passive"))
      (node (ref "C59") (pin "1") (pinfunction "1_1") (pintype "passive"))
      (node (ref "C60") (pin "1") (pinfunction "1_1") (pintype "passive"))
      (node (ref "IC1") (pin "1") (pinfunction "VIN_1") (pintype "input"))
      (node (ref "R25") (pin "2") (pinfunction "2_2") (pintype "passive"))
      (node (ref "T2") (pin "E") (pinfunction "E_E") (pintype "passive"))
      (node (ref "T3") (pin "E") (pinfunction "E_E") (pintype "passive"))
      (node (ref "U$3") (pin "7") (pinfunction "7_7") (pintype "bidirectional"))
      (node (ref "U$3") (pin "9") (pinfunction "9_9") (pintype "bidirectional"))
      (node (ref "U$4") (pin "10") (pinfunction "10_10") (pintype "bidirectional"))
      (node (ref "U$4") (pin "8") (pinfunction "8_8") (pintype "bidirectional"))
      (node (ref "VNQ5027AK-E1") (pin "P$1") (pinfunction "VCC_P$1") (pintype "bidirectional"))
      (node (ref "VNQ5027AK-E1") (pin "P$12") (pinfunction "VCC_1_P$12") (pintype "bidirectional"))
      (node (ref "VNQ5027AK-E1") (pin "P$25") (pinfunction "VCC_PAD_P$25") (pintype "bidirectional"))
    )
    (net (code "141") (name "SWCLK") (class "Default")
      (node (ref "U$5") (pin "3") (pinfunction "3_3") (pintype "passive"))
      (node (ref "U4") (pin "PA14") (pinfunction "PA14_PA14") (pintype "bidirectional"))
    )
    (net (code "142") (name "SWDIO") (class "Default")
      (node (ref "U$5") (pin "4") (pinfunction "4_4") (pintype "passive"))
      (node (ref "U4") (pin "PA13") (pinfunction "PA13_PA13") (pintype "bidirectional"))
    )
    (net (code "143") (name "SWO") (class "Default")
      (node (ref "U$5") (pin "2") (pinfunction "2_2") (pintype "passive"))
    )
    (net (code "144") (name "TENSO") (class "Default")
      (node (ref "C56") (pin "1") (pinfunction "1_1") (pintype "passive"))
      (node (ref "R31") (pin "2") (pinfunction "2_2") (pintype "passive"))
      (node (ref "U9") (pin "9") (pinfunction "AIN7_9") (pintype "input"))
    )
    (net (code "145") (name "TENSO_IN+") (class "Default")
      (node (ref "J3") (pin "1") (pinfunction "S_1") (pintype "passive"))
      (node (ref "R29") (pin "1") (pinfunction "1_1") (pintype "passive"))
    )
    (net (code "146") (name "TENSO_IN-") (class "Default")
      (node (ref "J3") (pin "2") (pinfunction "S_2") (pintype "passive"))
      (node (ref "R30") (pin "1") (pinfunction "1_1") (pintype "passive"))
    )
    (net (code "147") (name "VBAT") (class "Default")
      (node (ref "C27") (pin "1") (pinfunction "1_1") (pintype "passive"))
      (node (ref "C48") (pin "1") (pinfunction "1_1") (pintype "passive"))
      (node (ref "U$32") (pin "+") (pinfunction "+_+") (pintype "bidirectional"))
      (node (ref "U4") (pin "VBAT") (pinfunction "VBAT_VBAT") (pintype "power_in"))
    )
    (net (code "148") (name "WATCHDOG") (class "Default")
      (node (ref "U$3") (pin "15") (pinfunction "15_15") (pintype "bidirectional"))
      (node (ref "U$4") (pin "16") (pinfunction "16_16") (pintype "bidirectional"))
    )
    (net (code "149") (name "XBEE_RX") (class "Default")
      (node (ref "U$6") (pin "2") (pinfunction "DOUT_2") (pintype "output"))
      (node (ref "U4") (pin "PA10") (pinfunction "PA10_PA10") (pintype "bidirectional"))
    )
    (net (code "150") (name "XBEE_TX") (class "Default")
      (node (ref "U$6") (pin "3") (pinfunction "DIN_3") (pintype "input"))
      (node (ref "U4") (pin "PA9") (pinfunction "PA9_PA9") (pintype "bidirectional"))
    )
    (net (code "151") (name "unconnected-(U$6-CTS-Pad12)") (class "Default")
      (node (ref "U$6") (pin "12") (pinfunction "CTS_12") (pintype "output"))
    )
    (net (code "152") (name "unconnected-(U$6-DIO0-Pad20)") (class "Default")
      (node (ref "U$6") (pin "20") (pinfunction "DIO0_20") (pintype "bidirectional"))
    )
    (net (code "153") (name "unconnected-(U$6-DIO1-Pad19)") (class "Default")
      (node (ref "U$6") (pin "19") (pinfunction "DIO1_19") (pintype "bidirectional"))
    )
    (net (code "154") (name "unconnected-(U$6-DIO2-Pad18)") (class "Default")
      (node (ref "U$6") (pin "18") (pinfunction "DIO2_18") (pintype "bidirectional"))
    )
    (net (code "155") (name "unconnected-(U$6-DIO3-Pad17)") (class "Default")
      (node (ref "U$6") (pin "17") (pinfunction "DIO3_17") (pintype "bidirectional"))
    )
    (net (code "156") (name "unconnected-(U$6-DIO4-Pad11)") (class "Default")
      (node (ref "U$6") (pin "11") (pinfunction "DIO4_11") (pintype "bidirectional"))
    )
    (net (code "157") (name "unconnected-(U$6-DIO9-Pad13)") (class "Default")
      (node (ref "U$6") (pin "13") (pinfunction "DIO9_13") (pintype "bidirectional"))
    )
    (net (code "158") (name "unconnected-(U$6-DIO11-Pad7)") (class "Default")
      (node (ref "U$6") (pin "7") (pinfunction "DIO11_7") (pintype "bidirectional"))
    )
    (net (code "159") (name "unconnected-(U$6-DIO12-Pad4)") (class "Default")
      (node (ref "U$6") (pin "4") (pinfunction "DIO12_4") (pintype "bidirectional"))
    )
    (net (code "160") (name "unconnected-(U$6-DTR-Pad9)") (class "Default")
      (node (ref "U$6") (pin "9") (pinfunction "DTR_9") (pintype "bidirectional"))
    )
    (net (code "161") (name "unconnected-(U$6-RES-Pad8)") (class "Default")
      (node (ref "U$6") (pin "8") (pinfunction "RES_8") (pintype "bidirectional"))
    )
    (net (code "162") (name "unconnected-(U$6-RES-Pad14)") (class "Default")
      (node (ref "U$6") (pin "14") (pinfunction "RES_14") (pintype "bidirectional"))
    )
    (net (code "163") (name "unconnected-(U$6-RTS-Pad16)") (class "Default")
      (node (ref "U$6") (pin "16") (pinfunction "RTS_16") (pintype "input"))
    )
    (net (code "164") (name "unconnected-(U$39-IO3{slash}~{RESET}-Pad1)") (class "Default")
      (node (ref "U$39") (pin "1") (pinfunction "IO3/~{RESET}_1") (pintype "bidirectional"))
    )
    (net (code "165") (name "unconnected-(U$39-~{WP}-Pad9)") (class "Default")
      (node (ref "U$39") (pin "9") (pinfunction "~{WP}_9") (pintype "bidirectional"))
    )
    (net (code "166") (name "unconnected-(U3-VREF-Pad5)") (class "Default")
      (node (ref "U3") (pin "5") (pinfunction "VREF_5") (pintype "output"))
    )
    (net (code "167") (name "unconnected-(U4-PadPH0-OSC_IN)") (class "Default")
      (node (ref "U4") (pin "PH0-OSC_IN") (pinfunction "PH0-OSC_IN_PH0-OSC_IN") (pintype "bidirectional"))
    )
    (net (code "168") (name "unconnected-(U4-PadPH1-OSC_OUT)") (class "Default")
      (node (ref "U4") (pin "PH1-OSC_OUT") (pinfunction "PH1-OSC_OUT_PH1-OSC_OUT") (pintype "bidirectional"))
    )
    (net (code "169") (name "unconnected-(U8-VREF-Pad5)") (class "Default")
      (node (ref "U8") (pin "5") (pinfunction "VREF_5") (pintype "output"))
    )
    (net (code "170") (name "unconnected-(U9-AIN1{slash}P3-Pad1)") (class "Default")
      (node (ref "U9") (pin "1") (pinfunction "AIN1/P3_1") (pintype "bidirectional"))
    )
    (net (code "171") (name "unconnected-(U9-AIN2{slash}P2-Pad2)") (class "Default")
      (node (ref "U9") (pin "2") (pinfunction "AIN2/P2_2") (pintype "bidirectional"))
    )
    (net (code "172") (name "unconnected-(U9-AIN3{slash}P1{slash}REFIN2(+)-Pad3)") (class "Default")
      (node (ref "U9") (pin "3") (pinfunction "AIN3/P1/REFIN2(+)_3") (pintype "bidirectional"))
    )
    (net (code "173") (name "unconnected-(U9-AIN4{slash}P0{slash}REFIN2(?)-Pad4)") (class "Default")
      (node (ref "U9") (pin "4") (pinfunction "AIN4/P0/REFIN2(?)_4") (pintype "bidirectional"))
    )
    (net (code "174") (name "unconnected-(U9-AIN5-Pad7)") (class "Default")
      (node (ref "U9") (pin "7") (pinfunction "AIN5_7") (pintype "input"))
    )
    (net (code "175") (name "unconnected-(U9-AIN6-Pad8)") (class "Default")
      (node (ref "U9") (pin "8") (pinfunction "AIN6_8") (pintype "input"))
    )
    (net (code "176") (name "unconnected-(U9-AIN8-Pad10)") (class "Default")
      (node (ref "U9") (pin "10") (pinfunction "AIN8_10") (pintype "input"))
    )
    (net (code "177") (name "unconnected-(U9-AIN9-Pad11)") (class "Default")
      (node (ref "U9") (pin "11") (pinfunction "AIN9_11") (pintype "input"))
    )
    (net (code "178") (name "unconnected-(U9-AIN10-Pad12)") (class "Default")
      (node (ref "U9") (pin "12") (pinfunction "AIN10_12") (pintype "input"))
    )
    (net (code "179") (name "unconnected-(U9-AIN11-Pad13)") (class "Default")
      (node (ref "U9") (pin "13") (pinfunction "AIN11_13") (pintype "input"))
    )
    (net (code "180") (name "unconnected-(U9-AIN12-Pad14)") (class "Default")
      (node (ref "U9") (pin "14") (pinfunction "AIN12_14") (pintype "input"))
    )
    (net (code "181") (name "unconnected-(U9-AIN13-Pad15)") (class "Default")
      (node (ref "U9") (pin "15") (pinfunction "AIN13_15") (pintype "input"))
    )
    (net (code "182") (name "unconnected-(U9-AIN16-Pad20)") (class "Default")
      (node (ref "U9") (pin "20") (pinfunction "AIN16_20") (pintype "input"))
    )
    (net (code "183") (name "unconnected-(U9-MCLK1-Pad29)") (class "Default")
      (node (ref "U9") (pin "29") (pinfunction "MCLK1_29") (pintype "input"))
    )
    (net (code "184") (name "unconnected-(U9-MCLK2-Pad30)") (class "Default")
      (node (ref "U9") (pin "30") (pinfunction "MCLK2_30") (pintype "input"))
    )
    (net (code "185") (name "unconnected-(U9-NC-Pad26)") (class "Default")
      (node (ref "U9") (pin "26") (pinfunction "NC_26") (pintype "no_connect"))
    )
    (net (code "186") (name "unconnected-(U11-AUX_CL-Pad7)") (class "Default")
      (node (ref "U11") (pin "7") (pinfunction "AUX_CL_7") (pintype "bidirectional"))
    )
    (net (code "187") (name "unconnected-(U11-AUX_DA-Pad21)") (class "Default")
      (node (ref "U11") (pin "21") (pinfunction "AUX_DA_21") (pintype "bidirectional"))
    )
    (net (code "188") (name "unconnected-(U11-FSYNC-Pad11)") (class "Default")
      (node (ref "U11") (pin "11") (pinfunction "FSYNC_11") (pintype "bidirectional"))
    )
    (net (code "189") (name "unconnected-(U11-NC-Pad2)") (class "Default")
      (node (ref "U11") (pin "2") (pinfunction "NC_2") (pintype "bidirectional"))
    )
    (net (code "190") (name "unconnected-(U11-NC-Pad3)") (class "Default")
      (node (ref "U11") (pin "3") (pinfunction "NC_3") (pintype "bidirectional"))
    )
    (net (code "191") (name "unconnected-(U11-NC-Pad4)") (class "Default")
      (node (ref "U11") (pin "4") (pinfunction "NC_4") (pintype "bidirectional"))
    )
    (net (code "192") (name "unconnected-(U11-NC-Pad5)") (class "Default")
      (node (ref "U11") (pin "5") (pinfunction "NC_5") (pintype "bidirectional"))
    )
    (net (code "193") (name "unconnected-(U11-NC-Pad6)") (class "Default")
      (node (ref "U11") (pin "6") (pinfunction "NC_6") (pintype "bidirectional"))
    )
    (net (code "194") (name "unconnected-(U11-NC-Pad14)") (class "Default")
      (node (ref "U11") (pin "14") (pinfunction "NC_14") (pintype "bidirectional"))
    )
    (net (code "195") (name "unconnected-(U11-NC-Pad15)") (class "Default")
      (node (ref "U11") (pin "15") (pinfunction "NC_15") (pintype "bidirectional"))
    )
    (net (code "196") (name "unconnected-(U11-NC-Pad16)") (class "Default")
      (node (ref "U11") (pin "16") (pinfunction "NC_16") (pintype "bidirectional"))
    )
    (net (code "197") (name "unconnected-(U11-NC-Pad17)") (class "Default")
      (node (ref "U11") (pin "17") (pinfunction "NC_17") (pintype "bidirectional"))
    )
    (net (code "198") (name "unconnected-(U11-RESV-Pad19)") (class "Default")
      (node (ref "U11") (pin "19") (pinfunction "RESV_19") (pintype "bidirectional"))
    )
    (net (code "199") (name "unconnected-(U12-NC-Pad17)") (class "Default")
      (node (ref "U12") (pin "17") (pinfunction "NC_17") (pintype "no_connect"))
    )
  )
)
